# Netzteil_Darlington_v2.net
KiCad netlist of a schematic drawn in EAGLE
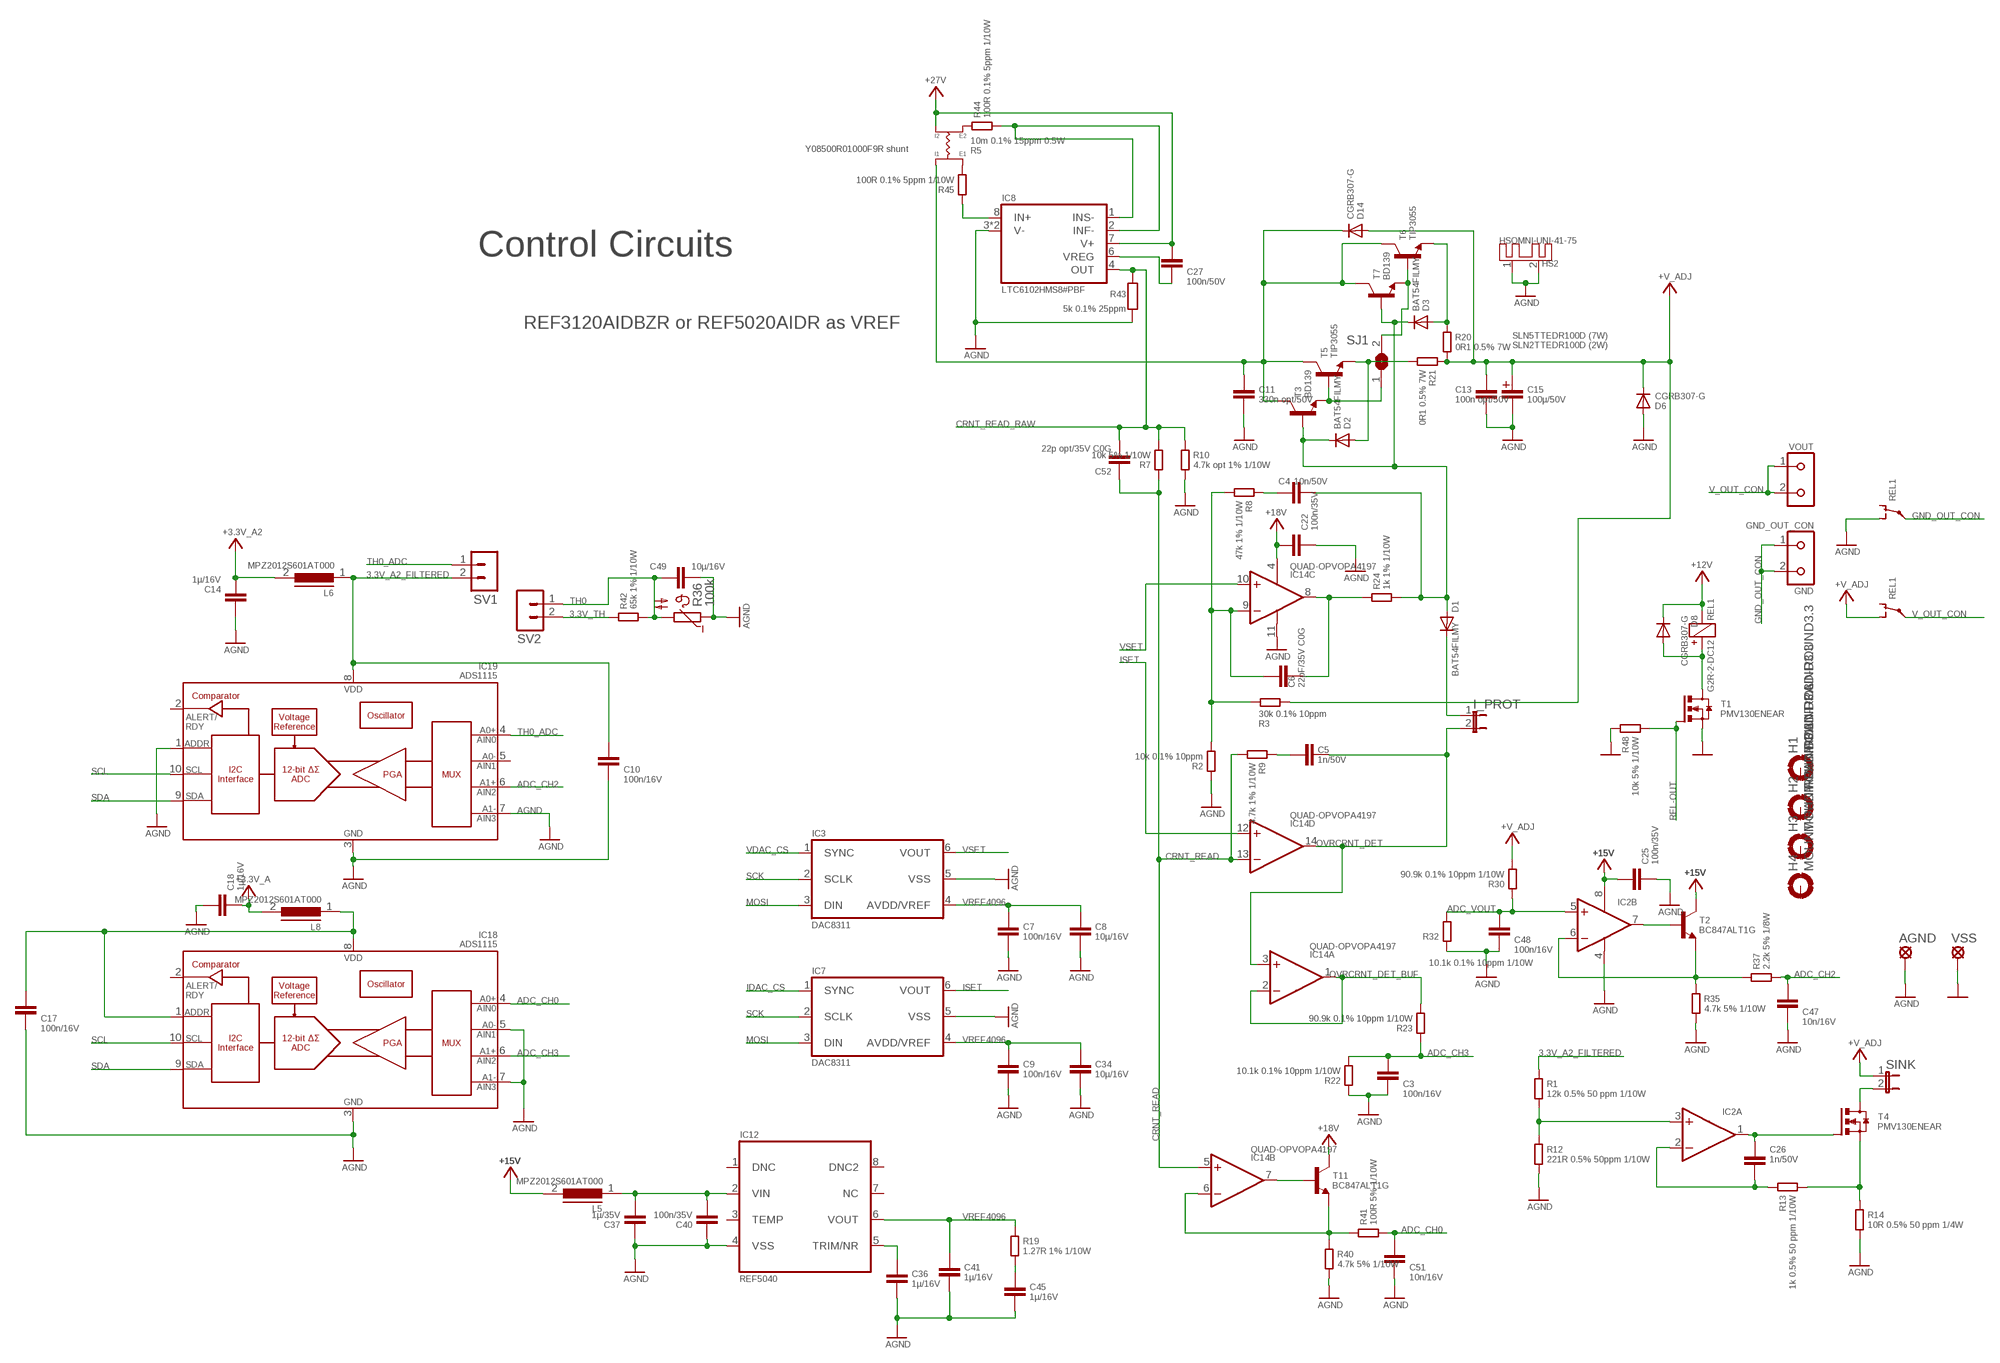
[diagram p0: schematic, sheet 1]
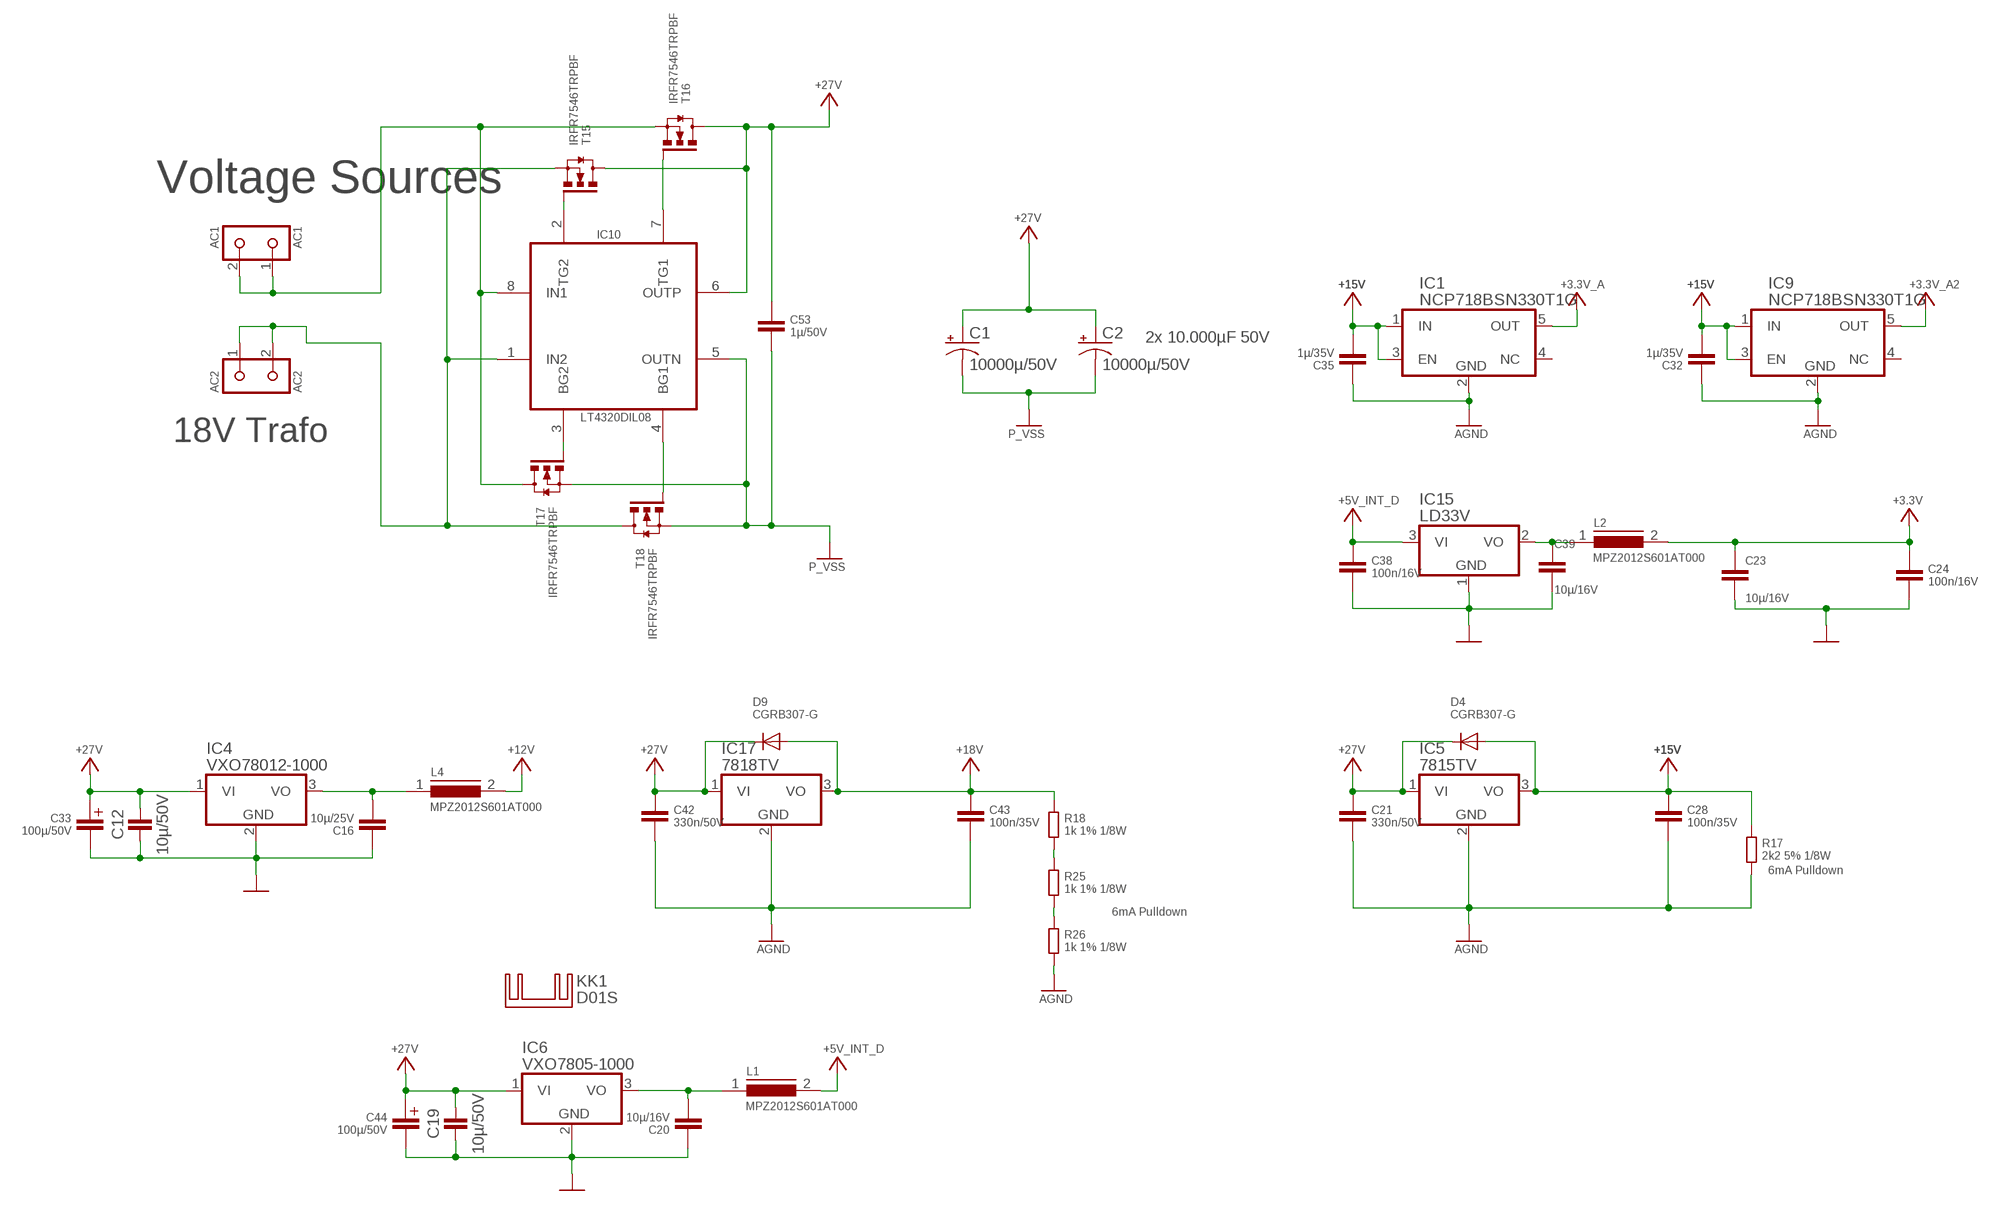
[diagram p1: schematic, sheet 2]
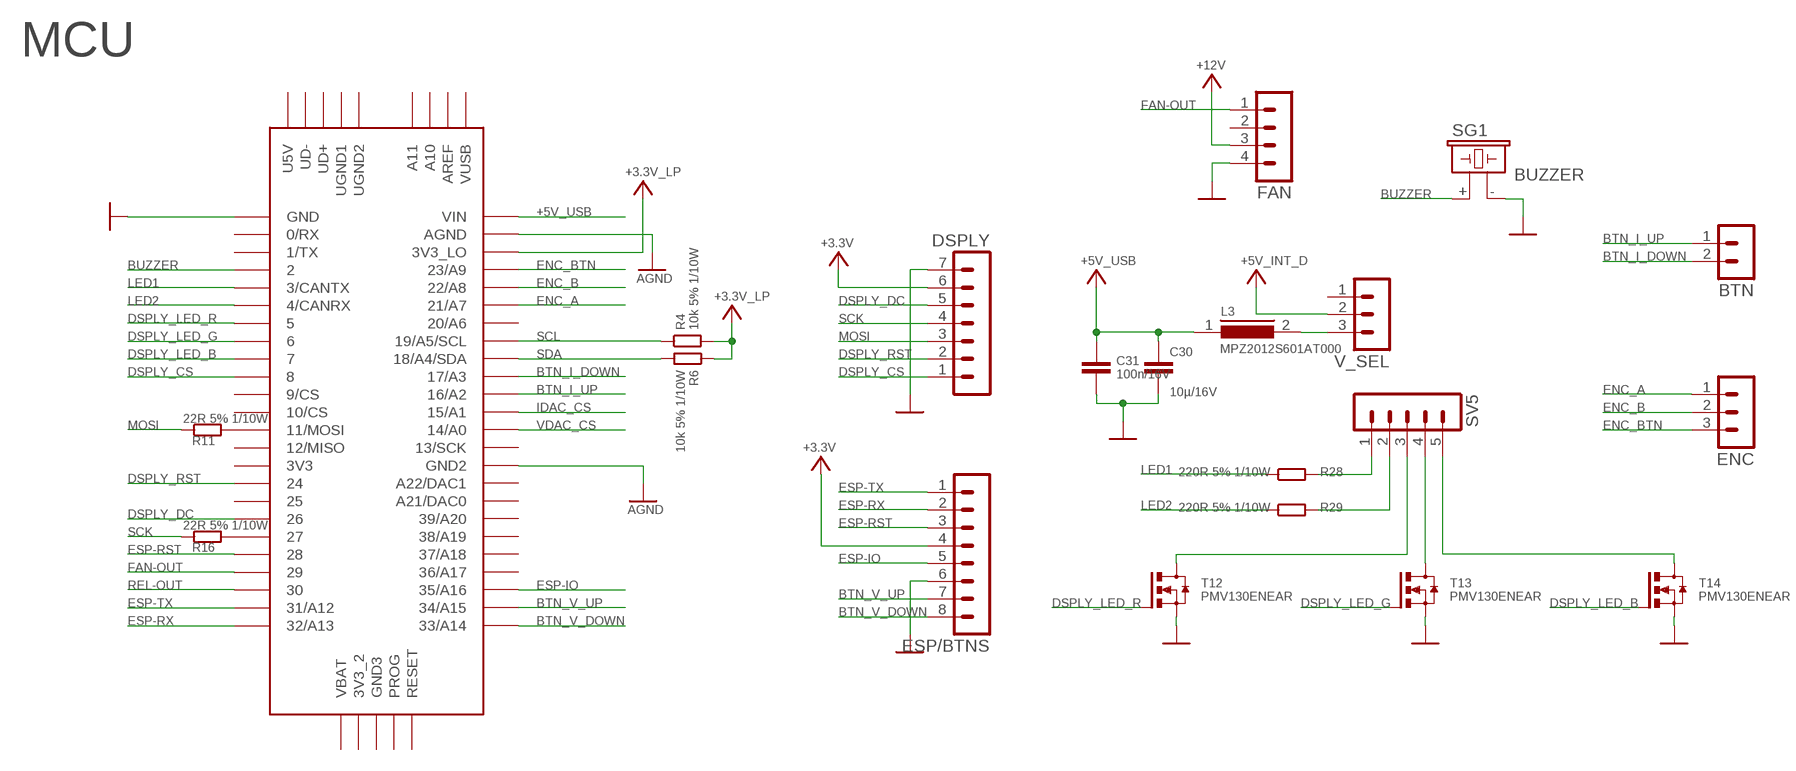
[diagram p2: schematic, sheet 3]

(export (version "E")
  (design (tool "Eeschema 10.0.6"))
  (components
    (comp (ref "AGND")
      (value "LSP13")
      (footprint "eagle-import:LSP13")
      (libsource (lib "eagle-import") (part "LSP13"))
    )
    (comp (ref "C3")
      (value "100n/16V")
      (footprint "eagle-import:0805")
      (libsource (lib "eagle-import") (part "CC/0805"))
    )
    (comp (ref "C4")
      (value "10n/50V")
      (footprint "eagle-import:0805")
      (libsource (lib "eagle-import") (part "CC/0805"))
    )
    (comp (ref "C5")
      (value "1n/50V")
      (footprint "eagle-import:0805")
      (libsource (lib "eagle-import") (part "CC/0805"))
    )
    (comp (ref "C6")
      (value "22pF/35V C0G")
      (footprint "eagle-import:0805")
      (libsource (lib "eagle-import") (part "CC/0805"))
    )
    (comp (ref "C7")
      (value "100n/16V")
      (footprint "eagle-import:0805")
      (libsource (lib "eagle-import") (part "CC/0805"))
    )
    (comp (ref "C8")
      (value "10µ/16V")
      (footprint "eagle-import:1206")
      (libsource (lib "eagle-import") (part "CC/1206"))
    )
    (comp (ref "C9")
      (value "100n/16V")
      (footprint "eagle-import:0805")
      (libsource (lib "eagle-import") (part "CC/0805"))
    )
    (comp (ref "C10")
      (value "100n/16V")
      (footprint "eagle-import:0805")
      (libsource (lib "eagle-import") (part "CC/0805"))
    )
    (comp (ref "C11")
      (value "330n opt/50V")
      (footprint "eagle-import:0805")
      (libsource (lib "eagle-import") (part "CC/0805"))
    )
    (comp (ref "C13")
      (value "100n opt/50V")
      (footprint "eagle-import:0805")
      (libsource (lib "eagle-import") (part "CC/0805"))
    )
    (comp (ref "C14")
      (value "1µ/16V")
      (footprint "eagle-import:0805")
      (libsource (lib "eagle-import") (part "CC/0805"))
    )
    (comp (ref "C15")
      (value "100µ/50V")
      (footprint "eagle-import:C+_3.5_8")
      (libsource (lib "eagle-import") (part "C+3.5/8"))
    )
    (comp (ref "C17")
      (value "100n/16V")
      (footprint "eagle-import:0805")
      (libsource (lib "eagle-import") (part "CC/0805"))
    )
    (comp (ref "C18")
      (value "1µ/16V")
      (footprint "eagle-import:0805")
      (libsource (lib "eagle-import") (part "CC/0805"))
    )
    (comp (ref "C22")
      (value "100n/35V")
      (footprint "eagle-import:0805")
      (libsource (lib "eagle-import") (part "CC/0805"))
    )
    (comp (ref "C25")
      (value "100n/35V")
      (footprint "eagle-import:0805")
      (libsource (lib "eagle-import") (part "CC/0805"))
    )
    (comp (ref "C26")
      (value "1n/50V")
      (footprint "eagle-import:0805")
      (libsource (lib "eagle-import") (part "CC/0805"))
    )
    (comp (ref "C27")
      (value "100n/50V")
      (footprint "eagle-import:0805")
      (libsource (lib "eagle-import") (part "CC/0805"))
    )
    (comp (ref "C34")
      (value "10µ/16V")
      (footprint "eagle-import:1206")
      (libsource (lib "eagle-import") (part "CC/1206"))
    )
    (comp (ref "C36")
      (value "1µ/16V")
      (footprint "eagle-import:0805")
      (libsource (lib "eagle-import") (part "CC/0805"))
    )
    (comp (ref "C37")
      (value "1µ/35V")
      (footprint "eagle-import:0805")
      (libsource (lib "eagle-import") (part "CC/0805"))
    )
    (comp (ref "C40")
      (value "100n/35V")
      (footprint "eagle-import:0805")
      (libsource (lib "eagle-import") (part "CC/0805"))
    )
    (comp (ref "C41")
      (value "1µ/16V")
      (footprint "eagle-import:0805")
      (libsource (lib "eagle-import") (part "CC/0805"))
    )
    (comp (ref "C45")
      (value "1µ/16V")
      (footprint "eagle-import:0805")
      (libsource (lib "eagle-import") (part "CC/0805"))
    )
    (comp (ref "C47")
      (value "10n/16V")
      (footprint "eagle-import:0805")
      (libsource (lib "eagle-import") (part "CC/0805"))
    )
    (comp (ref "C48")
      (value "100n/16V")
      (footprint "eagle-import:0805")
      (libsource (lib "eagle-import") (part "CC/0805"))
    )
    (comp (ref "C49")
      (value "10µ/16V")
      (footprint "eagle-import:1206")
      (libsource (lib "eagle-import") (part "CC/1206"))
    )
    (comp (ref "C51")
      (value "10n/16V")
      (footprint "eagle-import:0805")
      (libsource (lib "eagle-import") (part "CC/0805"))
    )
    (comp (ref "C52")
      (value "22p opt/35V C0G")
      (footprint "eagle-import:0805")
      (libsource (lib "eagle-import") (part "CC/0805"))
    )
    (comp (ref "D1")
      (value "BAT54FILMY")
      (footprint "eagle-import:SOT23")
      (libsource (lib "eagle-import") (part "DBAT54FILMY"))
    )
    (comp (ref "D2")
      (value "BAT54FILMY")
      (footprint "eagle-import:SOT23")
      (libsource (lib "eagle-import") (part "DBAT54FILMY"))
    )
    (comp (ref "D3")
      (value "BAT54FILMY")
      (footprint "eagle-import:SOT23")
      (libsource (lib "eagle-import") (part "DBAT54FILMY"))
    )
    (comp (ref "D6")
      (value "CGRB307-G")
      (footprint "eagle-import:DO214AA-CGRB307-G")
      (libsource (lib "eagle-import") (part "DWIDE"))
    )
    (comp (ref "D8")
      (value "CGRB307-G")
      (footprint "eagle-import:DO214AA-CGRB307-G")
      (libsource (lib "eagle-import") (part "DWIDE"))
    )
    (comp (ref "D14")
      (value "CGRB307-G")
      (footprint "eagle-import:DO214AA-CGRB307-G")
      (libsource (lib "eagle-import") (part "DWIDE"))
    )
    (comp (ref "GND_OUT_CON")
      (value "GND")
      (footprint "eagle-import:KL2-691311500002")
      (libsource (lib "eagle-import") (part "KL2691311500002"))
    )
    (comp (ref "H1")
      (value "MOUNT-PAD-ROUND3.3")
      (footprint "eagle-import:3,3-PAD")
      (libsource (lib "eagle-import") (part "MOUNT-PAD-ROUND3.3"))
    )
    (comp (ref "H2")
      (value "MOUNT-PAD-ROUND3.3")
      (footprint "eagle-import:3,3-PAD")
      (libsource (lib "eagle-import") (part "MOUNT-PAD-ROUND3.3"))
    )
    (comp (ref "H3")
      (value "MOUNT-PAD-ROUND3.3")
      (footprint "eagle-import:3,3-PAD")
      (libsource (lib "eagle-import") (part "MOUNT-PAD-ROUND3.3"))
    )
    (comp (ref "H4")
      (value "MOUNT-PAD-ROUND3.3")
      (footprint "eagle-import:3,3-PAD")
      (libsource (lib "eagle-import") (part "MOUNT-PAD-ROUND3.3"))
    )
    (comp (ref "HS2")
      (value "HSOMNI-UNI-41-75")
      (footprint "eagle-import:OMNI-UNI-41-75")
      (libsource (lib "eagle-import") (part "HSOMNI-UNI-41-75"))
    )
    (comp (ref "IC2")
      (value "DUAL-OPVSOP8")
      (footprint "eagle-import:SOP8")
      (libsource (lib "eagle-import") (part "DUAL-OPVSOP8"))
    )
    (comp (ref "IC3")
      (value "DAC8311")
      (footprint "eagle-import:SC-70-6")
      (libsource (lib "eagle-import") (part "DAC8X11"))
    )
    (comp (ref "IC7")
      (value "DAC8311")
      (footprint "eagle-import:SC-70-6")
      (libsource (lib "eagle-import") (part "DAC8X11"))
    )
    (comp (ref "IC8")
      (value "LTC6102HMS8#PBF")
      (footprint "eagle-import:MSOP8-0.65-3X3MM")
      (libsource (lib "eagle-import") (part "LTC6102"))
    )
    (comp (ref "IC12")
      (value "REF5040")
      (footprint "eagle-import:MSOP8-0.65-3X3MM")
      (libsource (lib "eagle-import") (part "REF50XXVSSOP8"))
    )
    (comp (ref "IC14")
      (value "QUAD-OPVOPA4197")
      (footprint "eagle-import:SO14")
      (libsource (lib "eagle-import") (part "QUAD-OPVOPA4197"))
    )
    (comp (ref "IC18")
      (value "ADS1115")
      (footprint "eagle-import:MSOP10")
      (libsource (lib "eagle-import") (part "ADS1015"))
    )
    (comp (ref "IC19")
      (value "ADS1115")
      (footprint "eagle-import:MSOP10")
      (libsource (lib "eagle-import") (part "ADS1015"))
    )
    (comp (ref "I_PROT")
      (value "JP1E")
      (footprint "eagle-import:JP1")
      (libsource (lib "eagle-import") (part "JP1E"))
    )
    (comp (ref "L5")
      (value "MPZ2012S601AT000")
      (footprint "eagle-import:C0805K")
      (libsource (lib "eagle-import") (part "L0805"))
    )
    (comp (ref "L6")
      (value "MPZ2012S601AT000")
      (footprint "eagle-import:C0805K")
      (libsource (lib "eagle-import") (part "L0805"))
    )
    (comp (ref "L8")
      (value "MPZ2012S601AT000")
      (footprint "eagle-import:C0805K")
      (libsource (lib "eagle-import") (part "L0805"))
    )
    (comp (ref "R1")
      (value "12k 0.5% 50 ppm 1/10W")
      (footprint "eagle-import:C0805K")
      (libsource (lib "eagle-import") (part "R-SMD0805"))
    )
    (comp (ref "R2")
      (value "10k 0.1% 10ppm")
      (footprint "eagle-import:C0805K")
      (libsource (lib "eagle-import") (part "R-SMD0805"))
    )
    (comp (ref "R3")
      (value "30k 0.1% 10ppm")
      (footprint "eagle-import:C0805K")
      (libsource (lib "eagle-import") (part "R-SMD0805"))
    )
    (comp (ref "R5")
      (value "10m 0.1% 15ppm 0.5W")
      (footprint "eagle-import:CSM2512")
      (libsource (lib "eagle-import") (part "R-CSM2512"))
    )
    (comp (ref "R7")
      (value "10k 5% 1/10W")
      (footprint "eagle-import:C0805K")
      (libsource (lib "eagle-import") (part "R-SMD0805"))
    )
    (comp (ref "R8")
      (value "47k 1% 1/10W")
      (footprint "eagle-import:C0805K")
      (libsource (lib "eagle-import") (part "R-SMD0805"))
    )
    (comp (ref "R9")
      (value "4.7k 1% 1/10W")
      (footprint "eagle-import:C0805K")
      (libsource (lib "eagle-import") (part "R-SMD0805"))
    )
    (comp (ref "R10")
      (value "4.7k opt 1% 1/10W")
      (footprint "eagle-import:C0805K")
      (libsource (lib "eagle-import") (part "R-SMD0805"))
    )
    (comp (ref "R12")
      (value "221R 0.5% 50ppm 1/10W")
      (footprint "eagle-import:C0805K")
      (libsource (lib "eagle-import") (part "R-SMD0805"))
    )
    (comp (ref "R13")
      (value "1k 0.5% 50 ppm 1/10W")
      (footprint "eagle-import:C0805K")
      (libsource (lib "eagle-import") (part "R-SMD0805"))
    )
    (comp (ref "R14")
      (value "10R 0.5% 50 ppm 1/4W")
      (footprint "eagle-import:C0805K")
      (libsource (lib "eagle-import") (part "R-SMD0805"))
    )
    (comp (ref "R19")
      (value "1.27R 1% 1/10W")
      (footprint "eagle-import:C0805K")
      (libsource (lib "eagle-import") (part "R-SMD0805"))
    )
    (comp (ref "R20")
      (value "0R1 0.5% 7W")
      (footprint "eagle-import:SLN2")
      (libsource (lib "eagle-import") (part "R-SMDSLN2"))
    )
    (comp (ref "R21")
      (value "0R1 0.5% 7W")
      (footprint "eagle-import:SLN2")
      (libsource (lib "eagle-import") (part "R-SMDSLN2"))
    )
    (comp (ref "R22")
      (value "10.1k 0.1% 10ppm 1/10W")
      (footprint "eagle-import:C0805K")
      (libsource (lib "eagle-import") (part "R-SMD0805"))
    )
    (comp (ref "R23")
      (value "90.9k 0.1% 10ppm 1/10W")
      (footprint "eagle-import:C0805K")
      (libsource (lib "eagle-import") (part "R-SMD0805"))
    )
    (comp (ref "R24")
      (value "1k 1% 1/10W")
      (footprint "eagle-import:C0805K")
      (libsource (lib "eagle-import") (part "R-SMD0805"))
    )
    (comp (ref "R30")
      (value "90.9k 0.1% 10ppm 1/10W")
      (footprint "eagle-import:C0805K")
      (libsource (lib "eagle-import") (part "R-SMD0805"))
    )
    (comp (ref "R32")
      (value "10.1k 0.1% 10ppm 1/10W")
      (footprint "eagle-import:C0805K")
      (libsource (lib "eagle-import") (part "R-SMD0805"))
    )
    (comp (ref "R35")
      (value "4.7k 5% 1/10W")
      (footprint "eagle-import:C0805K")
      (libsource (lib "eagle-import") (part "R-SMD0805"))
    )
    (comp (ref "R36")
      (value "100k")
      (footprint "eagle-import:P640")
      (libsource (lib "eagle-import") (part "NTC640"))
    )
    (comp (ref "R37")
      (value "2.2k 5% 1/8W")
      (footprint "eagle-import:C0805K")
      (libsource (lib "eagle-import") (part "R-SMD0805"))
    )
    (comp (ref "R40")
      (value "4.7k 5% 1/10W")
      (footprint "eagle-import:C0805K")
      (libsource (lib "eagle-import") (part "R-SMD0805"))
    )
    (comp (ref "R41")
      (value "100R 5% 1/10W")
      (footprint "eagle-import:C0805K")
      (libsource (lib "eagle-import") (part "R-SMD0805"))
    )
    (comp (ref "R42")
      (value "65k 1% 1/10W")
      (footprint "eagle-import:C0805K")
      (libsource (lib "eagle-import") (part "R-SMD0805"))
    )
    (comp (ref "R43")
      (value "5k 0.1% 25ppm")
      (footprint "eagle-import:R1206")
      (libsource (lib "eagle-import") (part "R-EU_R1206"))
    )
    (comp (ref "R44")
      (value "100R 0.1% 5ppm 1/10W")
      (footprint "eagle-import:C0805K")
      (libsource (lib "eagle-import") (part "R-SMD0805"))
    )
    (comp (ref "R45")
      (value "100R 0.1% 5ppm 1/10W")
      (footprint "eagle-import:C0805K")
      (libsource (lib "eagle-import") (part "R-SMD0805"))
    )
    (comp (ref "R48")
      (value "10k 5% 1/10W")
      (footprint "eagle-import:C0805K")
      (libsource (lib "eagle-import") (part "R-SMD0805"))
    )
    (comp (ref "REL1")
      (value "G2R-2-DC12")
      (footprint "eagle-import:REL-G2R2")
      (fields (field (name "OC_MOUSER") "653-G2R-2-DC12"))
      (libsource (lib "eagle-import") (part "REL-2UG2R2"))
    )
    (comp (ref "SINK")
      (value "JP1E")
      (footprint "eagle-import:JP1")
      (libsource (lib "eagle-import") (part "JP1E"))
    )
    (comp (ref "SJ1") (value "SJ") (footprint "eagle-import:SJ") (libsource (lib "eagle-import") (part "SJ")))
    (comp (ref "SV1")
      (value "JST-PH-2.0-2P")
      (footprint "eagle-import:JST-PH-2.0-2P")
      (libsource (lib "eagle-import") (part "JST-PH-2.0-2P"))
    )
    (comp (ref "SV2")
      (value "JST-PH-2.0-2P")
      (footprint "eagle-import:JST-PH-2.0-2P")
      (libsource (lib "eagle-import") (part "JST-PH-2.0-2P"))
    )
    (comp (ref "T1")
      (value "PMV130ENEAR")
      (footprint "eagle-import:SOT23")
      (libsource (lib "eagle-import") (part "neumluc_T-NMOSIRLML2502PBF"))
    )
    (comp (ref "T2")
      (value "BC847ALT1G")
      (footprint "eagle-import:SOT23-BEC")
      (libsource (lib "eagle-import") (part "T-NPNSOT23-BEC"))
    )
    (comp (ref "T3")
      (value "BD139")
      (footprint "eagle-import:TO126")
      (libsource (lib "eagle-import") (part "T-NPNTO126-ECB"))
    )
    (comp (ref "T4")
      (value "PMV130ENEAR")
      (footprint "eagle-import:SOT23")
      (libsource (lib "eagle-import") (part "neumluc_T-NMOSIRLML2502PBF"))
    )
    (comp (ref "T5")
      (value "TIP3055")
      (footprint "eagle-import:TOP3AV")
      (libsource (lib "eagle-import") (part "T-NPNTOP3AV-BCE"))
    )
    (comp (ref "T6")
      (value "TIP3055")
      (footprint "eagle-import:TOP3AV")
      (libsource (lib "eagle-import") (part "T-NPNTOP3AV-BCE"))
    )
    (comp (ref "T7")
      (value "BD139")
      (footprint "eagle-import:TO126")
      (libsource (lib "eagle-import") (part "T-NPNTO126-ECB"))
    )
    (comp (ref "T11")
      (value "BC847ALT1G")
      (footprint "eagle-import:SOT23-BEC")
      (libsource (lib "eagle-import") (part "T-NPNSOT23-BEC"))
    )
    (comp (ref "VOUT")
      (value "KL2691311500002")
      (footprint "eagle-import:KL2-691311500002")
      (libsource (lib "eagle-import") (part "KL2691311500002"))
    )
    (comp (ref "VSS")
      (value "LSP13")
      (footprint "eagle-import:LSP13")
      (libsource (lib "eagle-import") (part "LSP13"))
    )
    (comp (ref "BTN")
      (value "JST-PH-2.0-2P")
      (footprint "eagle-import:JST-PH-2.0-2P")
      (libsource (lib "eagle-import") (part "JST-PH-2.0-2P"))
    )
    (comp (ref "C30")
      (value "10µ/16V")
      (footprint "eagle-import:1206")
      (libsource (lib "eagle-import") (part "CC/1206"))
    )
    (comp (ref "C31")
      (value "100n/16V")
      (footprint "eagle-import:0805")
      (libsource (lib "eagle-import") (part "CC/0805"))
    )
    (comp (ref "DSPLY")
      (value "JST-PH-2.0-7P")
      (footprint "eagle-import:JST-PH-2.0-7P")
      (libsource (lib "eagle-import") (part "JST-PH-2.0-7P"))
    )
    (comp (ref "ENC")
      (value "JST-PH-2.0-3P")
      (footprint "eagle-import:JST-PH-2.0-3P")
      (libsource (lib "eagle-import") (part "JST-PH-2.0-3P"))
    )
    (comp (ref "ESP/BTNS")
      (value "JST-PH-2.0-8P")
      (footprint "eagle-import:JST-PH-2.0-8P")
      (libsource (lib "eagle-import") (part "JST-PH-2.0-8P"))
    )
    (comp (ref "FAN")
      (value "JST-PH-2.0-4P")
      (footprint "eagle-import:JST-PH-2.0-4P")
      (libsource (lib "eagle-import") (part "JST-PH-2.0-4P"))
    )
    (comp (ref "L3")
      (value "MPZ2012S601AT000")
      (footprint "eagle-import:C0805K")
      (libsource (lib "eagle-import") (part "L0805"))
    )
    (comp (ref "R4")
      (value "10k 5% 1/10W")
      (footprint "eagle-import:C0805K")
      (libsource (lib "eagle-import") (part "R-SMD0805"))
    )
    (comp (ref "R6")
      (value "10k 5% 1/10W")
      (footprint "eagle-import:C0805K")
      (libsource (lib "eagle-import") (part "R-SMD0805"))
    )
    (comp (ref "R11")
      (value "22R 5% 1/10W")
      (footprint "eagle-import:C0805K")
      (libsource (lib "eagle-import") (part "R-SMD0805"))
    )
    (comp (ref "R16")
      (value "22R 5% 1/10W")
      (footprint "eagle-import:C0805K")
      (libsource (lib "eagle-import") (part "R-SMD0805"))
    )
    (comp (ref "R28")
      (value "220R 5% 1/10W")
      (footprint "eagle-import:C0805K")
      (libsource (lib "eagle-import") (part "R-SMD0805"))
    )
    (comp (ref "R29")
      (value "220R 5% 1/10W")
      (footprint "eagle-import:C0805K")
      (libsource (lib "eagle-import") (part "R-SMD0805"))
    )
    (comp (ref "SG1")
      (value "BUZZER")
      (footprint "eagle-import:254-EMB73-RO")
      (libsource (lib "eagle-import") (part "BUZZER"))
    )
    (comp (ref "SV5")
      (value "JST-PH-2.0-5P")
      (footprint "eagle-import:JST-PH-2.0-5P")
      (libsource (lib "eagle-import") (part "JST-PH-2.0-5P"))
    )
    (comp (ref "T12")
      (value "PMV130ENEAR")
      (footprint "eagle-import:SOT23")
      (libsource (lib "eagle-import") (part "T-NMOSIRLML2502PBF"))
    )
    (comp (ref "T13")
      (value "PMV130ENEAR")
      (footprint "eagle-import:SOT23")
      (libsource (lib "eagle-import") (part "T-NMOSIRLML2502PBF"))
    )
    (comp (ref "T14")
      (value "PMV130ENEAR")
      (footprint "eagle-import:SOT23")
      (libsource (lib "eagle-import") (part "T-NMOSIRLML2502PBF"))
    )
    (comp (ref "U$33")
      (value "TEENSY_3.5/3.6")
      (footprint "eagle-import:TEENSY_3.5_3.6")
      (libsource (lib "eagle-import") (part "TEENSY_3.5/3.6"))
    )
    (comp (ref "V_SEL")
      (value "MA03-1")
      (footprint "eagle-import:MA03-1")
      (libsource (lib "eagle-import") (part "MA03-1"))
    )
    (comp (ref "AC1")
      (value "AC1")
      (footprint "eagle-import:KL2-691311500002")
      (libsource (lib "eagle-import") (part "KL2691311500002"))
    )
    (comp (ref "AC2")
      (value "AC2")
      (footprint "eagle-import:KL2-691311500002")
      (libsource (lib "eagle-import") (part "KL2691311500002"))
    )
    (comp (ref "C1")
      (value "10000µ/50V")
      (footprint "eagle-import:EB22,5D")
      (libsource (lib "eagle-import") (part "CPOL-USE10-22.5"))
    )
    (comp (ref "C2")
      (value "10000µ/50V")
      (footprint "eagle-import:EB22,5D")
      (libsource (lib "eagle-import") (part "CPOL-USE10-22.5"))
    )
    (comp (ref "C12")
      (value "10µ/50V")
      (footprint "eagle-import:C1210")
      (libsource (lib "eagle-import") (part "CAPACITOR-1210"))
    )
    (comp (ref "C16")
      (value "10µ/25V")
      (footprint "eagle-import:1206")
      (libsource (lib "eagle-import") (part "CC/1206"))
    )
    (comp (ref "C19")
      (value "10µ/50V")
      (footprint "eagle-import:C1210")
      (libsource (lib "eagle-import") (part "CAPACITOR-1210"))
    )
    (comp (ref "C20")
      (value "10µ/16V")
      (footprint "eagle-import:1206")
      (libsource (lib "eagle-import") (part "CC/1206"))
    )
    (comp (ref "C21")
      (value "330n/50V")
      (footprint "eagle-import:0805")
      (libsource (lib "eagle-import") (part "CC/0805"))
    )
    (comp (ref "C23")
      (value "10µ/16V")
      (footprint "eagle-import:1206")
      (libsource (lib "eagle-import") (part "CC/1206"))
    )
    (comp (ref "C24")
      (value "100n/16V")
      (footprint "eagle-import:0805")
      (libsource (lib "eagle-import") (part "CC/0805"))
    )
    (comp (ref "C28")
      (value "100n/35V")
      (footprint "eagle-import:0805")
      (libsource (lib "eagle-import") (part "CC/0805"))
    )
    (comp (ref "C32")
      (value "1µ/35V")
      (footprint "eagle-import:0805")
      (libsource (lib "eagle-import") (part "CC/0805"))
    )
    (comp (ref "C33")
      (value "100µ/50V")
      (footprint "eagle-import:C+_3.5_8")
      (libsource (lib "eagle-import") (part "C+3.5/8"))
    )
    (comp (ref "C35")
      (value "1µ/35V")
      (footprint "eagle-import:0805")
      (libsource (lib "eagle-import") (part "CC/0805"))
    )
    (comp (ref "C38")
      (value "100n/16V")
      (footprint "eagle-import:0805")
      (libsource (lib "eagle-import") (part "CC/0805"))
    )
    (comp (ref "C39")
      (value "10µ/16V")
      (footprint "eagle-import:1206")
      (libsource (lib "eagle-import") (part "CC/1206"))
    )
    (comp (ref "C42")
      (value "330n/50V")
      (footprint "eagle-import:0805")
      (libsource (lib "eagle-import") (part "CC/0805"))
    )
    (comp (ref "C43")
      (value "100n/35V")
      (footprint "eagle-import:0805")
      (libsource (lib "eagle-import") (part "CC/0805"))
    )
    (comp (ref "C44")
      (value "100µ/50V")
      (footprint "eagle-import:C+_3.5_8")
      (libsource (lib "eagle-import") (part "C+3.5/8"))
    )
    (comp (ref "C53")
      (value "1µ/50V")
      (footprint "eagle-import:1206")
      (libsource (lib "eagle-import") (part "CC/1206"))
    )
    (comp (ref "D4")
      (value "CGRB307-G")
      (footprint "eagle-import:DO214AA-CGRB307-G")
      (libsource (lib "eagle-import") (part "DWIDE"))
    )
    (comp (ref "D9")
      (value "CGRB307-G")
      (footprint "eagle-import:DO214AA-CGRB307-G")
      (libsource (lib "eagle-import") (part "DWIDE"))
    )
    (comp (ref "IC1")
      (value "NCP718BSN330T1G")
      (footprint "eagle-import:SOT23-5")
      (libsource (lib "eagle-import") (part "NCP718"))
    )
    (comp (ref "IC4")
      (value "VXO78012-1000")
      (footprint "eagle-import:78XX-DC-DC")
      (libsource (lib "eagle-import") (part "78XX-DC-DC-UNI-VXO-OKI"))
    )
    (comp (ref "IC5")
      (value "7815TV")
      (footprint "eagle-import:TO220V")
      (libsource (lib "eagle-import") (part "linear_262_78TV15"))
    )
    (comp (ref "IC6")
      (value "VXO7805-1000")
      (footprint "eagle-import:78XX-DC-DC")
      (libsource (lib "eagle-import") (part "78XX-DC-DC-UNI-VXO-OKI"))
    )
    (comp (ref "IC9")
      (value "NCP718BSN330T1G")
      (footprint "eagle-import:SOT23-5")
      (libsource (lib "eagle-import") (part "NCP718"))
    )
    (comp (ref "IC10")
      (value "LT4320DIL08")
      (footprint "eagle-import:DIL08")
      (libsource (lib "eagle-import") (part "LT4320DIL08"))
    )
    (comp (ref "IC15")
      (value "LD33V")
      (footprint "eagle-import:TO220V")
      (libsource (lib "eagle-import") (part "LD33V"))
    )
    (comp (ref "IC17")
      (value "7818TV")
      (footprint "eagle-import:TO220V")
      (libsource (lib "eagle-import") (part "78TV18"))
    )
    (comp (ref "KK1")
      (value "D01S")
      (footprint "eagle-import:D01S")
      (libsource (lib "eagle-import") (part "D01S"))
    )
    (comp (ref "L1")
      (value "MPZ2012S601AT000")
      (footprint "eagle-import:C0805K")
      (libsource (lib "eagle-import") (part "L0805"))
    )
    (comp (ref "L2")
      (value "MPZ2012S601AT000")
      (footprint "eagle-import:C0805K")
      (libsource (lib "eagle-import") (part "L0805"))
    )
    (comp (ref "L4")
      (value "MPZ2012S601AT000")
      (footprint "eagle-import:C0805K")
      (libsource (lib "eagle-import") (part "L0805"))
    )
    (comp (ref "R17")
      (value "2k2 5% 1/8W")
      (footprint "eagle-import:C0805K")
      (libsource (lib "eagle-import") (part "R-SMD0805"))
    )
    (comp (ref "R18")
      (value "1k 1% 1/8W")
      (footprint "eagle-import:C0805K")
      (libsource (lib "eagle-import") (part "R-SMD0805"))
    )
    (comp (ref "R25")
      (value "1k 1% 1/8W")
      (footprint "eagle-import:C0805K")
      (libsource (lib "eagle-import") (part "R-SMD0805"))
    )
    (comp (ref "R26")
      (value "1k 1% 1/8W")
      (footprint "eagle-import:C0805K")
      (libsource (lib "eagle-import") (part "R-SMD0805"))
    )
    (comp (ref "T15")
      (value "IRFR7546TRPBF")
      (footprint "eagle-import:DPACK")
      (libsource (lib "eagle-import") (part "neumluc_T-NMOSNTD4963N"))
    )
    (comp (ref "T16")
      (value "IRFR7546TRPBF")
      (footprint "eagle-import:DPACK")
      (libsource (lib "eagle-import") (part "neumluc_T-NMOSNTD4963N"))
    )
    (comp (ref "T17")
      (value "IRFR7546TRPBF")
      (footprint "eagle-import:DPACK")
      (libsource (lib "eagle-import") (part "neumluc_T-NMOSNTD4963N"))
    )
    (comp (ref "T18")
      (value "IRFR7546TRPBF")
      (footprint "eagle-import:DPACK")
      (libsource (lib "eagle-import") (part "neumluc_T-NMOSNTD4963N"))
    )
  )
  (nets
    (net (code "1") (name "+3.3V") (class "Default")
      (node (ref "C23") (pin "1") (pinfunction "1_1") (pintype "passive"))
      (node (ref "C24") (pin "1") (pinfunction "1_1") (pintype "passive"))
      (node (ref "DSPLY") (pin "6") (pinfunction "6_6") (pintype "passive"))
      (node (ref "ESP/BTNS") (pin "4") (pinfunction "4_4") (pintype "passive"))
      (node (ref "L2") (pin "2") (pinfunction "2_2") (pintype "passive"))
    )
    (net (code "2") (name "+3.3V_A") (class "Default")
      (node (ref "C18") (pin "2") (pinfunction "2_2") (pintype "passive"))
      (node (ref "IC1") (pin "5") (pinfunction "OUT_5") (pintype "passive"))
      (node (ref "L8") (pin "2") (pinfunction "2_2") (pintype "passive"))
    )
    (net (code "3") (name "+3.3V_A2") (class "Default")
      (node (ref "C14") (pin "2") (pinfunction "2_2") (pintype "passive"))
      (node (ref "IC9") (pin "5") (pinfunction "OUT_5") (pintype "passive"))
      (node (ref "L6") (pin "2") (pinfunction "2_2") (pintype "passive"))
    )
    (net (code "4") (name "+3.3V_LP") (class "Default")
      (node (ref "R4") (pin "2") (pinfunction "2_2") (pintype "passive"))
      (node (ref "R6") (pin "1") (pinfunction "1_1") (pintype "passive"))
      (node (ref "U$33") (pin "3V3_LO") (pinfunction "3V3_LO_3V3_LO") (pintype "bidirectional"))
    )
    (net (code "5") (name "+5V_INT_D") (class "Default")
      (node (ref "C38") (pin "1") (pinfunction "1_1") (pintype "passive"))
      (node (ref "IC15") (pin "3") (pinfunction "VI_3") (pintype "input"))
      (node (ref "L1") (pin "2") (pinfunction "2_2") (pintype "passive"))
      (node (ref "V_SEL") (pin "2") (pinfunction "2_2") (pintype "passive"))
    )
    (net (code "6") (name "+5V_USB") (class "Default")
      (node (ref "C30") (pin "1") (pinfunction "1_1") (pintype "passive"))
      (node (ref "C31") (pin "1") (pinfunction "1_1") (pintype "passive"))
      (node (ref "L3") (pin "1") (pinfunction "1_1") (pintype "passive"))
      (node (ref "U$33") (pin "VIN") (pinfunction "VIN_VIN") (pintype "bidirectional"))
    )
    (net (code "7") (name "+12V") (class "Default")
      (node (ref "D8") (pin "C") (pinfunction "C_C") (pintype "passive"))
      (node (ref "FAN") (pin "3") (pinfunction "3_3") (pintype "passive"))
      (node (ref "L4") (pin "2") (pinfunction "2_2") (pintype "passive"))
      (node (ref "REL1") (pin "-") (pinfunction "-_-") (pintype "passive"))
    )
    (net (code "8") (name "+15V") (class "Default")
      (node (ref "C25") (pin "1") (pinfunction "1_1") (pintype "passive"))
      (node (ref "C28") (pin "1") (pinfunction "1_1") (pintype "passive"))
      (node (ref "C32") (pin "2") (pinfunction "2_2") (pintype "passive"))
      (node (ref "C35") (pin "2") (pinfunction "2_2") (pintype "passive"))
      (node (ref "D4") (pin "A") (pinfunction "A_A") (pintype "passive"))
      (node (ref "IC1") (pin "1") (pinfunction "IN_1") (pintype "input"))
      (node (ref "IC1") (pin "3") (pinfunction "EN_3") (pintype "input"))
      (node (ref "IC2") (pin "8") (pinfunction "V+_8") (pintype "power_in"))
      (node (ref "IC5") (pin "3") (pinfunction "VO_3") (pintype "passive"))
      (node (ref "IC9") (pin "1") (pinfunction "IN_1") (pintype "input"))
      (node (ref "IC9") (pin "3") (pinfunction "EN_3") (pintype "input"))
      (node (ref "L5") (pin "2") (pinfunction "2_2") (pintype "passive"))
      (node (ref "R17") (pin "1") (pinfunction "1_1") (pintype "passive"))
      (node (ref "T2") (pin "C") (pinfunction "C_C") (pintype "passive"))
    )
    (net (code "9") (name "+18V") (class "Default")
      (node (ref "C22") (pin "1") (pinfunction "1_1") (pintype "passive"))
      (node (ref "C43") (pin "1") (pinfunction "1_1") (pintype "passive"))
      (node (ref "D9") (pin "A") (pinfunction "A_A") (pintype "passive"))
      (node (ref "IC14") (pin "4") (pinfunction "V+_4") (pintype "power_in"))
      (node (ref "IC17") (pin "3") (pinfunction "VO_3") (pintype "passive"))
      (node (ref "R18") (pin "1") (pinfunction "1_1") (pintype "passive"))
      (node (ref "T11") (pin "C") (pinfunction "C_C") (pintype "passive"))
    )
    (net (code "10") (name "+27V") (class "Default")
      (node (ref "C1") (pin "+") (pinfunction "+_+") (pintype "passive"))
      (node (ref "C12") (pin "2") (pinfunction "2_2") (pintype "passive"))
      (node (ref "C19") (pin "2") (pinfunction "2_2") (pintype "passive"))
      (node (ref "C2") (pin "+") (pinfunction "+_+") (pintype "passive"))
      (node (ref "C21") (pin "1") (pinfunction "1_1") (pintype "passive"))
      (node (ref "C27") (pin "1") (pinfunction "1_1") (pintype "passive"))
      (node (ref "C33") (pin "+") (pinfunction "+_+") (pintype "passive"))
      (node (ref "C42") (pin "1") (pinfunction "1_1") (pintype "passive"))
      (node (ref "C44") (pin "+") (pinfunction "+_+") (pintype "passive"))
      (node (ref "C53") (pin "1") (pinfunction "1_1") (pintype "passive"))
      (node (ref "D4") (pin "C") (pinfunction "C_C") (pintype "passive"))
      (node (ref "D9") (pin "C") (pinfunction "C_C") (pintype "passive"))
      (node (ref "IC10") (pin "6") (pinfunction "OUTP_6") (pintype "bidirectional"))
      (node (ref "IC17") (pin "1") (pinfunction "VI_1") (pintype "input"))
      (node (ref "IC4") (pin "1") (pinfunction "VI_1") (pintype "input"))
      (node (ref "IC5") (pin "1") (pinfunction "VI_1") (pintype "input"))
      (node (ref "IC6") (pin "1") (pinfunction "VI_1") (pintype "input"))
      (node (ref "IC8") (pin "7") (pinfunction "V+_7") (pintype "power_in"))
      (node (ref "R5") (pin "I2") (pinfunction "I2_I2") (pintype "passive"))
      (node (ref "T15") (pin "3") (pinfunction "D_3") (pintype "passive"))
      (node (ref "T16") (pin "3") (pinfunction "D_3") (pintype "passive"))
    )
    (net (code "11") (name "+V_ADJ") (class "Default")
      (node (ref "C13") (pin "1") (pinfunction "1_1") (pintype "passive"))
      (node (ref "C15") (pin "+") (pinfunction "+_+") (pintype "passive"))
      (node (ref "D14") (pin "A") (pinfunction "A_A") (pintype "passive"))
      (node (ref "D6") (pin "C") (pinfunction "C_C") (pintype "passive"))
      (node (ref "R20") (pin "2") (pinfunction "2_2") (pintype "passive"))
      (node (ref "R21") (pin "1") (pinfunction "1_1") (pintype "passive"))
      (node (ref "R3") (pin "1") (pinfunction "1_1") (pintype "passive"))
      (node (ref "R30") (pin "2") (pinfunction "2_2") (pintype "passive"))
      (node (ref "REL1") (pin "S1") (pinfunction "S_S1") (pintype "passive"))
      (node (ref "SINK") (pin "1") (pinfunction "1_1") (pintype "passive"))
    )
    (net (code "12") (name "3.3V_A2_FILTERED") (class "Default")
      (node (ref "C10") (pin "1") (pinfunction "1_1") (pintype "passive"))
      (node (ref "IC19") (pin "8") (pinfunction "VDD_8") (pintype "bidirectional"))
      (node (ref "L6") (pin "1") (pinfunction "1_1") (pintype "passive"))
      (node (ref "R1") (pin "1") (pinfunction "1_1") (pintype "passive"))
      (node (ref "SV1") (pin "2") (pinfunction "2_2") (pintype "passive"))
    )
    (net (code "13") (name "3.3V_TH") (class "Default")
      (node (ref "R42") (pin "1") (pinfunction "1_1") (pintype "passive"))
      (node (ref "SV2") (pin "2") (pinfunction "2_2") (pintype "passive"))
    )
    (net (code "14") (name "ADC_CH0") (class "Default")
      (node (ref "C51") (pin "1") (pinfunction "1_1") (pintype "passive"))
      (node (ref "IC18") (pin "4") (pinfunction "AIN0_4") (pintype "bidirectional"))
      (node (ref "R41") (pin "2") (pinfunction "2_2") (pintype "passive"))
    )
    (net (code "15") (name "ADC_CH2") (class "Default")
      (node (ref "C47") (pin "1") (pinfunction "1_1") (pintype "passive"))
      (node (ref "IC19") (pin "6") (pinfunction "AIN2_6") (pintype "bidirectional"))
      (node (ref "R37") (pin "2") (pinfunction "2_2") (pintype "passive"))
    )
    (net (code "16") (name "ADC_CH3") (class "Default")
      (node (ref "C3") (pin "1") (pinfunction "1_1") (pintype "passive"))
      (node (ref "IC18") (pin "6") (pinfunction "AIN2_6") (pintype "bidirectional"))
      (node (ref "R22") (pin "2") (pinfunction "2_2") (pintype "passive"))
      (node (ref "R23") (pin "1") (pinfunction "1_1") (pintype "passive"))
    )
    (net (code "17") (name "ADC_VOUT") (class "Default")
      (node (ref "C48") (pin "1") (pinfunction "1_1") (pintype "passive"))
      (node (ref "IC2") (pin "5") (pinfunction "+IN_5") (pintype "input"))
      (node (ref "R30") (pin "1") (pinfunction "1_1") (pintype "passive"))
      (node (ref "R32") (pin "2") (pinfunction "2_2") (pintype "passive"))
    )
    (net (code "18") (name "AGND") (class "Default")
      (node (ref "AGND") (pin "MP") (pinfunction "MP_MP") (pintype "passive"))
      (node (ref "C10") (pin "2") (pinfunction "2_2") (pintype "passive"))
      (node (ref "C11") (pin "2") (pinfunction "2_2") (pintype "passive"))
      (node (ref "C13") (pin "2") (pinfunction "2_2") (pintype "passive"))
      (node (ref "C14") (pin "1") (pinfunction "1_1") (pintype "passive"))
      (node (ref "C15") (pin "-") (pinfunction "-_-") (pintype "passive"))
      (node (ref "C17") (pin "2") (pinfunction "2_2") (pintype "passive"))
      (node (ref "C18") (pin "1") (pinfunction "1_1") (pintype "passive"))
      (node (ref "C21") (pin "2") (pinfunction "2_2") (pintype "passive"))
      (node (ref "C22") (pin "2") (pinfunction "2_2") (pintype "passive"))
      (node (ref "C25") (pin "2") (pinfunction "2_2") (pintype "passive"))
      (node (ref "C28") (pin "2") (pinfunction "2_2") (pintype "passive"))
      (node (ref "C3") (pin "2") (pinfunction "2_2") (pintype "passive"))
      (node (ref "C32") (pin "1") (pinfunction "1_1") (pintype "passive"))
      (node (ref "C34") (pin "2") (pinfunction "2_2") (pintype "passive"))
      (node (ref "C35") (pin "1") (pinfunction "1_1") (pintype "passive"))
      (node (ref "C36") (pin "2") (pinfunction "2_2") (pintype "passive"))
      (node (ref "C37") (pin "1") (pinfunction "1_1") (pintype "passive"))
      (node (ref "C40") (pin "1") (pinfunction "1_1") (pintype "passive"))
      (node (ref "C41") (pin "2") (pinfunction "2_2") (pintype "passive"))
      (node (ref "C42") (pin "2") (pinfunction "2_2") (pintype "passive"))
      (node (ref "C43") (pin "2") (pinfunction "2_2") (pintype "passive"))
      (node (ref "C45") (pin "2") (pinfunction "2_2") (pintype "passive"))
      (node (ref "C47") (pin "2") (pinfunction "2_2") (pintype "passive"))
      (node (ref "C48") (pin "2") (pinfunction "2_2") (pintype "passive"))
      (node (ref "C49") (pin "1") (pinfunction "1_1") (pintype "passive"))
      (node (ref "C51") (pin "2") (pinfunction "2_2") (pintype "passive"))
      (node (ref "C7") (pin "2") (pinfunction "2_2") (pintype "passive"))
      (node (ref "C8") (pin "2") (pinfunction "2_2") (pintype "passive"))
      (node (ref "C9") (pin "2") (pinfunction "2_2") (pintype "passive"))
      (node (ref "D6") (pin "A") (pinfunction "A_A") (pintype "passive"))
      (node (ref "HS2") (pin "1") (pinfunction "1_1") (pintype "passive"))
      (node (ref "HS2") (pin "2") (pinfunction "2_2") (pintype "passive"))
      (node (ref "IC1") (pin "2") (pinfunction "GND_2") (pintype "passive"))
      (node (ref "IC12") (pin "4") (pinfunction "VSS_4") (pintype "power_in"))
      (node (ref "IC14") (pin "11") (pinfunction "V-_11") (pintype "power_in"))
      (node (ref "IC17") (pin "2") (pinfunction "GND_2") (pintype "passive"))
      (node (ref "IC18") (pin "3") (pinfunction "VSS_3") (pintype "bidirectional"))
      (node (ref "IC18") (pin "5") (pinfunction "AIN1_5") (pintype "bidirectional"))
      (node (ref "IC18") (pin "7") (pinfunction "AIN3_7") (pintype "bidirectional"))
      (node (ref "IC19") (pin "1") (pinfunction "ADDR_1") (pintype "bidirectional"))
      (node (ref "IC19") (pin "3") (pinfunction "VSS_3") (pintype "bidirectional"))
      (node (ref "IC19") (pin "7") (pinfunction "AIN3_7") (pintype "bidirectional"))
      (node (ref "IC2") (pin "4") (pinfunction "V-_4") (pintype "power_in"))
      (node (ref "IC3") (pin "5") (pinfunction "VSS_5") (pintype "power_in"))
      (node (ref "IC5") (pin "2") (pinfunction "GND_2") (pintype "passive"))
      (node (ref "IC7") (pin "5") (pinfunction "VSS_5") (pintype "power_in"))
      (node (ref "IC8") (pin "3") (pinfunction "V-_3") (pintype "power_in"))
      (node (ref "IC8") (pin "5") (pinfunction "V-_5") (pintype "power_in"))
      (node (ref "IC9") (pin "2") (pinfunction "GND_2") (pintype "passive"))
      (node (ref "R10") (pin "2") (pinfunction "2_2") (pintype "passive"))
      (node (ref "R12") (pin "2") (pinfunction "2_2") (pintype "passive"))
      (node (ref "R14") (pin "2") (pinfunction "2_2") (pintype "passive"))
      (node (ref "R17") (pin "2") (pinfunction "2_2") (pintype "passive"))
      (node (ref "R2") (pin "1") (pinfunction "1_1") (pintype "passive"))
      (node (ref "R22") (pin "1") (pinfunction "1_1") (pintype "passive"))
      (node (ref "R26") (pin "2") (pinfunction "2_2") (pintype "passive"))
      (node (ref "R32") (pin "1") (pinfunction "1_1") (pintype "passive"))
      (node (ref "R35") (pin "2") (pinfunction "2_2") (pintype "passive"))
      (node (ref "R36") (pin "1") (pinfunction "1_1") (pintype "passive"))
      (node (ref "R40") (pin "2") (pinfunction "2_2") (pintype "passive"))
      (node (ref "R43") (pin "1") (pinfunction "1_1") (pintype "passive"))
      (node (ref "REL1") (pin "S2") (pinfunction "S_S2") (pintype "passive"))
      (node (ref "U$33") (pin "AGND") (pinfunction "AGND_AGND") (pintype "bidirectional"))
      (node (ref "U$33") (pin "GND2") (pinfunction "GND2_GND2") (pintype "bidirectional"))
    )
    (net (code "19") (name "BTN_I_DOWN") (class "Default")
      (node (ref "BTN") (pin "2") (pinfunction "2_2") (pintype "passive"))
      (node (ref "U$33") (pin "17/A3") (pinfunction "17/A3_17/A3") (pintype "bidirectional"))
    )
    (net (code "20") (name "BTN_I_UP") (class "Default")
      (node (ref "BTN") (pin "1") (pinfunction "1_1") (pintype "passive"))
      (node (ref "U$33") (pin "16/A2") (pinfunction "16/A2_16/A2") (pintype "bidirectional"))
    )
    (net (code "21") (name "BTN_V_DOWN") (class "Default")
      (node (ref "ESP/BTNS") (pin "8") (pinfunction "8_8") (pintype "passive"))
      (node (ref "U$33") (pin "33/A14") (pinfunction "33/A14_33/A14") (pintype "bidirectional"))
    )
    (net (code "22") (name "BTN_V_UP") (class "Default")
      (node (ref "ESP/BTNS") (pin "7") (pinfunction "7_7") (pintype "passive"))
      (node (ref "U$33") (pin "34/A15") (pinfunction "34/A15_34/A15") (pintype "bidirectional"))
    )
    (net (code "23") (name "BUZZER") (class "Default")
      (node (ref "SG1") (pin "+") (pinfunction "1_+") (pintype "passive"))
      (node (ref "U$33") (pin "2") (pinfunction "2_2") (pintype "bidirectional"))
    )
    (net (code "24") (name "CRNT_READ") (class "Default")
      (node (ref "C52") (pin "1") (pinfunction "1_1") (pintype "passive"))
      (node (ref "IC14") (pin "13") (pinfunction "-IN_13") (pintype "input"))
      (node (ref "IC14") (pin "5") (pinfunction "+IN_5") (pintype "input"))
      (node (ref "R7") (pin "1") (pinfunction "1_1") (pintype "passive"))
      (node (ref "R9") (pin "2") (pinfunction "2_2") (pintype "passive"))
    )
    (net (code "25") (name "CRNT_READ_RAW") (class "Default")
      (node (ref "C52") (pin "2") (pinfunction "2_2") (pintype "passive"))
      (node (ref "IC8") (pin "4") (pinfunction "OUT_4") (pintype "bidirectional"))
      (node (ref "R10") (pin "1") (pinfunction "1_1") (pintype "passive"))
      (node (ref "R43") (pin "2") (pinfunction "2_2") (pintype "passive"))
      (node (ref "R7") (pin "2") (pinfunction "2_2") (pintype "passive"))
    )
    (net (code "26") (name "DSPLY_CS") (class "Default")
      (node (ref "DSPLY") (pin "1") (pinfunction "1_1") (pintype "passive"))
      (node (ref "U$33") (pin "8") (pinfunction "8_8") (pintype "bidirectional"))
    )
    (net (code "27") (name "DSPLY_DC") (class "Default")
      (node (ref "DSPLY") (pin "5") (pinfunction "5_5") (pintype "passive"))
      (node (ref "U$33") (pin "26") (pinfunction "26_26") (pintype "bidirectional"))
    )
    (net (code "28") (name "DSPLY_LED_B") (class "Default")
      (node (ref "T14") (pin "1") (pinfunction "G_1") (pintype "passive"))
      (node (ref "U$33") (pin "7") (pinfunction "7_7") (pintype "bidirectional"))
    )
    (net (code "29") (name "DSPLY_LED_G") (class "Default")
      (node (ref "T13") (pin "1") (pinfunction "G_1") (pintype "passive"))
      (node (ref "U$33") (pin "6") (pinfunction "6_6") (pintype "bidirectional"))
    )
    (net (code "30") (name "DSPLY_LED_R") (class "Default")
      (node (ref "T12") (pin "1") (pinfunction "G_1") (pintype "passive"))
      (node (ref "U$33") (pin "5") (pinfunction "5_5") (pintype "bidirectional"))
    )
    (net (code "31") (name "DSPLY_RST") (class "Default")
      (node (ref "DSPLY") (pin "2") (pinfunction "2_2") (pintype "passive"))
      (node (ref "U$33") (pin "24") (pinfunction "24_24") (pintype "bidirectional"))
    )
    (net (code "32") (name "ENC_A") (class "Default")
      (node (ref "ENC") (pin "1") (pinfunction "1_1") (pintype "passive"))
      (node (ref "U$33") (pin "21/A7") (pinfunction "21/A7_21/A7") (pintype "bidirectional"))
    )
    (net (code "33") (name "ENC_B") (class "Default")
      (node (ref "ENC") (pin "2") (pinfunction "2_2") (pintype "passive"))
      (node (ref "U$33") (pin "22/A8") (pinfunction "22/A8_22/A8") (pintype "bidirectional"))
    )
    (net (code "34") (name "ENC_BTN") (class "Default")
      (node (ref "ENC") (pin "3") (pinfunction "3_3") (pintype "passive"))
      (node (ref "U$33") (pin "23/A9") (pinfunction "23/A9_23/A9") (pintype "bidirectional"))
    )
    (net (code "35") (name "ESP-IO") (class "Default")
      (node (ref "ESP/BTNS") (pin "5") (pinfunction "5_5") (pintype "passive"))
      (node (ref "U$33") (pin "35/A16") (pinfunction "35/A16_35/A16") (pintype "bidirectional"))
    )
    (net (code "36") (name "ESP-RST") (class "Default")
      (node (ref "ESP/BTNS") (pin "3") (pinfunction "3_3") (pintype "passive"))
      (node (ref "U$33") (pin "28") (pinfunction "28_28") (pintype "bidirectional"))
    )
    (net (code "37") (name "ESP-RX") (class "Default")
      (node (ref "ESP/BTNS") (pin "2") (pinfunction "2_2") (pintype "passive"))
      (node (ref "U$33") (pin "32/A13") (pinfunction "32/A13_32/A13") (pintype "bidirectional"))
    )
    (net (code "38") (name "ESP-TX") (class "Default")
      (node (ref "ESP/BTNS") (pin "1") (pinfunction "1_1") (pintype "passive"))
      (node (ref "U$33") (pin "31/A12") (pinfunction "31/A12_31/A12") (pintype "bidirectional"))
    )
    (net (code "39") (name "FAN-OUT") (class "Default")
      (node (ref "FAN") (pin "1") (pinfunction "1_1") (pintype "passive"))
      (node (ref "U$33") (pin "29") (pinfunction "29_29") (pintype "bidirectional"))
    )
    (net (code "40") (name "GND_OUT_CON") (class "Default")
      (node (ref "GND_OUT_CON") (pin "1") (pinfunction "1_1") (pintype "passive"))
      (node (ref "GND_OUT_CON") (pin "2") (pinfunction "2_2") (pintype "passive"))
      (node (ref "REL1") (pin "P2") (pinfunction "P_P2") (pintype "passive"))
    )
    (net (code "41") (name "IDAC_CS") (class "Default")
      (node (ref "IC7") (pin "1") (pinfunction "SYNC_1") (pintype "input"))
      (node (ref "U$33") (pin "15/A1") (pinfunction "15/A1_15/A1") (pintype "bidirectional"))
    )
    (net (code "42") (name "ISET") (class "Default")
      (node (ref "IC14") (pin "12") (pinfunction "+IN_12") (pintype "input"))
      (node (ref "IC7") (pin "6") (pinfunction "VOUT_6") (pintype "output"))
    )
    (net (code "43") (name "LED1") (class "Default")
      (node (ref "R28") (pin "1") (pinfunction "1_1") (pintype "passive"))
      (node (ref "U$33") (pin "3/CANTX") (pinfunction "3/CANTX_3/CANTX") (pintype "bidirectional"))
    )
    (net (code "44") (name "LED2") (class "Default")
      (node (ref "R29") (pin "1") (pinfunction "1_1") (pintype "passive"))
      (node (ref "U$33") (pin "4/CANRX") (pinfunction "4/CANRX_4/CANRX") (pintype "bidirectional"))
    )
    (net (code "45") (name "MOSI") (class "Default")
      (node (ref "DSPLY") (pin "3") (pinfunction "3_3") (pintype "passive"))
      (node (ref "IC3") (pin "3") (pinfunction "DIN_3") (pintype "bidirectional"))
      (node (ref "IC7") (pin "3") (pinfunction "DIN_3") (pintype "bidirectional"))
      (node (ref "R11") (pin "1") (pinfunction "1_1") (pintype "passive"))
    )
    (net (code "46") (name "Net-(C4-Pad1)") (class "Default")
      (node (ref "C4") (pin "1") (pinfunction "1_1") (pintype "passive"))
      (node (ref "R8") (pin "1") (pinfunction "1_1") (pintype "passive"))
    )
    (net (code "47") (name "Net-(C5-Pad1)") (class "Default")
      (node (ref "C5") (pin "1") (pinfunction "1_1") (pintype "passive"))
      (node (ref "R9") (pin "1") (pinfunction "1_1") (pintype "passive"))
    )
    (net (code "48") (name "Net-(C45-Pad1)") (class "Default")
      (node (ref "C45") (pin "1") (pinfunction "1_1") (pintype "passive"))
      (node (ref "R19") (pin "2") (pinfunction "2_2") (pintype "passive"))
    )
    (net (code "49") (name "Net-(D1-A)") (class "Default")
      (node (ref "C4") (pin "2") (pinfunction "2_2") (pintype "passive"))
      (node (ref "D1") (pin "1") (pinfunction "A_1") (pintype "passive"))
      (node (ref "D2") (pin "3") (pinfunction "C_3") (pintype "passive"))
      (node (ref "D3") (pin "3") (pinfunction "C_3") (pintype "passive"))
      (node (ref "R24") (pin "2") (pinfunction "2_2") (pintype "passive"))
      (node (ref "T3") (pin "3") (pinfunction "B_3") (pintype "passive"))
      (node (ref "T7") (pin "3") (pinfunction "B_3") (pintype "passive"))
    )
    (net (code "50") (name "Net-(D1-C)") (class "Default")
      (node (ref "D1") (pin "3") (pinfunction "C_3") (pintype "passive"))
      (node (ref "I_PROT") (pin "1") (pinfunction "1_1") (pintype "passive"))
    )
    (net (code "51") (name "Net-(D2-A)") (class "Default")
      (node (ref "D2") (pin "1") (pinfunction "A_1") (pintype "passive"))
      (node (ref "R21") (pin "2") (pinfunction "2_2") (pintype "passive"))
      (node (ref "T5") (pin "E") (pinfunction "E_E") (pintype "passive"))
    )
    (net (code "52") (name "Net-(D3-A)") (class "Default")
      (node (ref "D3") (pin "1") (pinfunction "A_1") (pintype "passive"))
      (node (ref "R20") (pin "1") (pinfunction "1_1") (pintype "passive"))
      (node (ref "T6") (pin "E") (pinfunction "E_E") (pintype "passive"))
    )
    (net (code "53") (name "Net-(IC2A-+IN)") (class "Default")
      (node (ref "IC2") (pin "3") (pinfunction "+IN_3") (pintype "input"))
      (node (ref "R1") (pin "2") (pinfunction "2_2") (pintype "passive"))
      (node (ref "R12") (pin "1") (pinfunction "1_1") (pintype "passive"))
    )
    (net (code "54") (name "Net-(IC2A--IN)") (class "Default")
      (node (ref "C26") (pin "2") (pinfunction "2_2") (pintype "passive"))
      (node (ref "IC2") (pin "2") (pinfunction "-IN_2") (pintype "input"))
      (node (ref "R13") (pin "1") (pinfunction "1_1") (pintype "passive"))
    )
    (net (code "55") (name "Net-(IC2A-OUT)") (class "Default")
      (node (ref "C26") (pin "1") (pinfunction "1_1") (pintype "passive"))
      (node (ref "IC2") (pin "1") (pinfunction "OUT_1") (pintype "output"))
      (node (ref "T4") (pin "1") (pinfunction "G_1") (pintype "passive"))
    )
    (net (code "56") (name "Net-(IC2B--IN)") (class "Default")
      (node (ref "IC2") (pin "6") (pinfunction "-IN_6") (pintype "input"))
      (node (ref "R35") (pin "1") (pinfunction "1_1") (pintype "passive"))
      (node (ref "R37") (pin "1") (pinfunction "1_1") (pintype "passive"))
      (node (ref "T2") (pin "E") (pinfunction "E_E") (pintype "passive"))
    )
    (net (code "57") (name "Net-(IC2B-OUT)") (class "Default")
      (node (ref "IC2") (pin "7") (pinfunction "OUT_7") (pintype "output"))
      (node (ref "T2") (pin "B") (pinfunction "B_B") (pintype "passive"))
    )
    (net (code "58") (name "Net-(IC4-VO)") (class "Default")
      (node (ref "C16") (pin "2") (pinfunction "2_2") (pintype "passive"))
      (node (ref "IC4") (pin "3") (pinfunction "VO_3") (pintype "passive"))
      (node (ref "L4") (pin "1") (pinfunction "1_1") (pintype "passive"))
    )
    (net (code "59") (name "Net-(IC6-VO)") (class "Default")
      (node (ref "C20") (pin "2") (pinfunction "2_2") (pintype "passive"))
      (node (ref "IC6") (pin "3") (pinfunction "VO_3") (pintype "passive"))
      (node (ref "L1") (pin "1") (pinfunction "1_1") (pintype "passive"))
    )
    (net (code "60") (name "Net-(IC8-IN+)") (class "Default")
      (node (ref "IC8") (pin "8") (pinfunction "IN+_8") (pintype "input"))
      (node (ref "R45") (pin "1") (pinfunction "1_1") (pintype "passive"))
    )
    (net (code "61") (name "Net-(IC8-INF-)") (class "Default")
      (node (ref "IC8") (pin "1") (pinfunction "INS-_1") (pintype "input"))
      (node (ref "IC8") (pin "2") (pinfunction "INF-_2") (pintype "bidirectional"))
      (node (ref "R44") (pin "2") (pinfunction "2_2") (pintype "passive"))
    )
    (net (code "62") (name "Net-(IC8-VREG)") (class "Default")
      (node (ref "C27") (pin "2") (pinfunction "2_2") (pintype "passive"))
      (node (ref "IC8") (pin "6") (pinfunction "VREG_6") (pintype "bidirectional"))
    )
    (net (code "63") (name "Net-(IC10-BG1)") (class "Default")
      (node (ref "IC10") (pin "4") (pinfunction "BG1_4") (pintype "bidirectional"))
      (node (ref "T18") (pin "1") (pinfunction "G_1") (pintype "passive"))
    )
    (net (code "64") (name "Net-(IC10-BG2)") (class "Default")
      (node (ref "IC10") (pin "3") (pinfunction "BG2_3") (pintype "bidirectional"))
      (node (ref "T17") (pin "1") (pinfunction "G_1") (pintype "passive"))
    )
    (net (code "65") (name "Net-(IC10-IN1)") (class "Default")
      (node (ref "AC1") (pin "1") (pinfunction "1_1") (pintype "passive"))
      (node (ref "AC1") (pin "2") (pinfunction "2_2") (pintype "passive"))
      (node (ref "IC10") (pin "8") (pinfunction "IN1_8") (pintype "bidirectional"))
      (node (ref "T16") (pin "2") (pinfunction "S_2") (pintype "passive"))
      (node (ref "T17") (pin "3") (pinfunction "D_3") (pintype "passive"))
    )
    (net (code "66") (name "Net-(IC10-IN2)") (class "Default")
      (node (ref "AC2") (pin "1") (pinfunction "1_1") (pintype "passive"))
      (node (ref "AC2") (pin "2") (pinfunction "2_2") (pintype "passive"))
      (node (ref "IC10") (pin "1") (pinfunction "IN2_1") (pintype "bidirectional"))
      (node (ref "T15") (pin "2") (pinfunction "S_2") (pintype "passive"))
      (node (ref "T18") (pin "3") (pinfunction "D_3") (pintype "passive"))
    )
    (net (code "67") (name "Net-(IC10-TG1)") (class "Default")
      (node (ref "IC10") (pin "7") (pinfunction "TG1_7") (pintype "bidirectional"))
      (node (ref "T16") (pin "1") (pinfunction "G_1") (pintype "passive"))
    )
    (net (code "68") (name "Net-(IC10-TG2)") (class "Default")
      (node (ref "IC10") (pin "2") (pinfunction "TG2_2") (pintype "bidirectional"))
      (node (ref "T15") (pin "1") (pinfunction "G_1") (pintype "passive"))
    )
    (net (code "69") (name "Net-(IC12-TRIM{slash}NR)") (class "Default")
      (node (ref "C36") (pin "1") (pinfunction "1_1") (pintype "passive"))
      (node (ref "IC12") (pin "5") (pinfunction "TRIM/NR_5") (pintype "output"))
    )
    (net (code "70") (name "Net-(IC12-VIN)") (class "Default")
      (node (ref "C37") (pin "2") (pinfunction "2_2") (pintype "passive"))
      (node (ref "C40") (pin "2") (pinfunction "2_2") (pintype "passive"))
      (node (ref "IC12") (pin "2") (pinfunction "VIN_2") (pintype "power_in"))
      (node (ref "L5") (pin "1") (pinfunction "1_1") (pintype "passive"))
    )
    (net (code "71") (name "Net-(IC14B--IN)") (class "Default")
      (node (ref "IC14") (pin "6") (pinfunction "-IN_6") (pintype "input"))
      (node (ref "R40") (pin "1") (pinfunction "1_1") (pintype "passive"))
      (node (ref "R41") (pin "1") (pinfunction "1_1") (pintype "passive"))
      (node (ref "T11") (pin "E") (pinfunction "E_E") (pintype "passive"))
    )
    (net (code "72") (name "Net-(IC14B-OUT)") (class "Default")
      (node (ref "IC14") (pin "7") (pinfunction "OUT_7") (pintype "output"))
      (node (ref "T11") (pin "B") (pinfunction "B_B") (pintype "passive"))
    )
    (net (code "73") (name "Net-(IC14C--IN)") (class "Default")
      (node (ref "C6") (pin "1") (pinfunction "1_1") (pintype "passive"))
      (node (ref "IC14") (pin "9") (pinfunction "-IN_9") (pintype "input"))
      (node (ref "R2") (pin "2") (pinfunction "2_2") (pintype "passive"))
      (node (ref "R3") (pin "2") (pinfunction "2_2") (pintype "passive"))
      (node (ref "R8") (pin "2") (pinfunction "2_2") (pintype "passive"))
    )
    (net (code "74") (name "Net-(IC14C-OUT)") (class "Default")
      (node (ref "C6") (pin "2") (pinfunction "2_2") (pintype "passive"))
      (node (ref "IC14") (pin "8") (pinfunction "OUT_8") (pintype "output"))
      (node (ref "R24") (pin "1") (pinfunction "1_1") (pintype "passive"))
    )
    (net (code "75") (name "Net-(IC15-VO)") (class "Default")
      (node (ref "C39") (pin "2") (pinfunction "2_2") (pintype "passive"))
      (node (ref "IC15") (pin "2") (pinfunction "VO_2") (pintype "passive"))
      (node (ref "L2") (pin "1") (pinfunction "1_1") (pintype "passive"))
    )
    (net (code "76") (name "Net-(IC18-ADDR)") (class "Default")
      (node (ref "C17") (pin "1") (pinfunction "1_1") (pintype "passive"))
      (node (ref "IC18") (pin "1") (pinfunction "ADDR_1") (pintype "bidirectional"))
      (node (ref "IC18") (pin "8") (pinfunction "VDD_8") (pintype "bidirectional"))
      (node (ref "L8") (pin "1") (pinfunction "1_1") (pintype "passive"))
    )
    (net (code "77") (name "Net-(L3-Pad2)") (class "Default")
      (node (ref "L3") (pin "2") (pinfunction "2_2") (pintype "passive"))
      (node (ref "V_SEL") (pin "3") (pinfunction "3_3") (pintype "passive"))
    )
    (net (code "78") (name "Net-(R11-Pad2)") (class "Default")
      (node (ref "R11") (pin "2") (pinfunction "2_2") (pintype "passive"))
      (node (ref "U$33") (pin "11/MOSI") (pinfunction "11/MOSI_11/MOSI") (pintype "bidirectional"))
    )
    (net (code "79") (name "Net-(R16-Pad2)") (class "Default")
      (node (ref "R16") (pin "2") (pinfunction "2_2") (pintype "passive"))
      (node (ref "U$33") (pin "27") (pinfunction "27_27") (pintype "bidirectional"))
    )
    (net (code "80") (name "Net-(R18-Pad2)") (class "Default")
      (node (ref "R18") (pin "2") (pinfunction "2_2") (pintype "passive"))
      (node (ref "R25") (pin "1") (pinfunction "1_1") (pintype "passive"))
    )
    (net (code "81") (name "Net-(R25-Pad2)") (class "Default")
      (node (ref "R25") (pin "2") (pinfunction "2_2") (pintype "passive"))
      (node (ref "R26") (pin "1") (pinfunction "1_1") (pintype "passive"))
    )
    (net (code "82") (name "Net-(R28-Pad2)") (class "Default")
      (node (ref "R28") (pin "2") (pinfunction "2_2") (pintype "passive"))
      (node (ref "SV5") (pin "1") (pinfunction "1_1") (pintype "passive"))
    )
    (net (code "83") (name "Net-(R29-Pad2)") (class "Default")
      (node (ref "R29") (pin "2") (pinfunction "2_2") (pintype "passive"))
      (node (ref "SV5") (pin "2") (pinfunction "2_2") (pintype "passive"))
    )
    (net (code "84") (name "Net-(R44-Pad1)") (class "Default")
      (node (ref "R44") (pin "1") (pinfunction "1_1") (pintype "passive"))
      (node (ref "R5") (pin "E2") (pinfunction "E2_E2") (pintype "passive"))
    )
    (net (code "85") (name "Net-(R45-Pad2)") (class "Default")
      (node (ref "R45") (pin "2") (pinfunction "2_2") (pintype "passive"))
      (node (ref "R5") (pin "E1") (pinfunction "E1_E1") (pintype "passive"))
    )
    (net (code "86") (name "Net-(T1-D)") (class "Default")
      (node (ref "D8") (pin "A") (pinfunction "A_A") (pintype "passive"))
      (node (ref "REL1") (pin "+") (pinfunction "+_+") (pintype "passive"))
      (node (ref "T1") (pin "3") (pinfunction "D_3") (pintype "passive"))
    )
    (net (code "87") (name "Net-(T3-C)") (class "Default")
      (node (ref "C11") (pin "1") (pinfunction "1_1") (pintype "passive"))
      (node (ref "D14") (pin "C") (pinfunction "C_C") (pintype "passive"))
      (node (ref "R5") (pin "I1") (pinfunction "I1_I1") (pintype "passive"))
      (node (ref "T3") (pin "2") (pinfunction "C_2") (pintype "passive"))
      (node (ref "T5") (pin "C") (pinfunction "C_C") (pintype "passive"))
      (node (ref "T6") (pin "C") (pinfunction "C_C") (pintype "passive"))
      (node (ref "T7") (pin "2") (pinfunction "C_2") (pintype "passive"))
    )
    (net (code "88") (name "Net-(T3-E)") (class "Default")
      (node (ref "SJ1") (pin "1") (pinfunction "1_1") (pintype "passive"))
      (node (ref "T3") (pin "1") (pinfunction "E_1") (pintype "passive"))
      (node (ref "T5") (pin "B") (pinfunction "B_B") (pintype "passive"))
    )
    (net (code "89") (name "Net-(T4-D)") (class "Default")
      (node (ref "SINK") (pin "2") (pinfunction "2_2") (pintype "passive"))
      (node (ref "T4") (pin "3") (pinfunction "D_3") (pintype "passive"))
    )
    (net (code "90") (name "Net-(T4-S)") (class "Default")
      (node (ref "R13") (pin "2") (pinfunction "2_2") (pintype "passive"))
      (node (ref "R14") (pin "1") (pinfunction "1_1") (pintype "passive"))
      (node (ref "T4") (pin "2") (pinfunction "S_2") (pintype "passive"))
    )
    (net (code "91") (name "Net-(T7-E)") (class "Default")
      (node (ref "SJ1") (pin "2") (pinfunction "2_2") (pintype "passive"))
      (node (ref "T6") (pin "B") (pinfunction "B_B") (pintype "passive"))
      (node (ref "T7") (pin "1") (pinfunction "E_1") (pintype "passive"))
    )
    (net (code "92") (name "Net-(T12-D)") (class "Default")
      (node (ref "SV5") (pin "3") (pinfunction "3_3") (pintype "passive"))
      (node (ref "T12") (pin "3") (pinfunction "D_3") (pintype "passive"))
    )
    (net (code "93") (name "Net-(T13-D)") (class "Default")
      (node (ref "SV5") (pin "4") (pinfunction "4_4") (pintype "passive"))
      (node (ref "T13") (pin "3") (pinfunction "D_3") (pintype "passive"))
    )
    (net (code "94") (name "Net-(T14-D)") (class "Default")
      (node (ref "SV5") (pin "5") (pinfunction "5_5") (pintype "passive"))
      (node (ref "T14") (pin "3") (pinfunction "D_3") (pintype "passive"))
    )
    (net (code "95") (name "OVRCRNT_DET") (class "Default")
      (node (ref "C5") (pin "2") (pinfunction "2_2") (pintype "passive"))
      (node (ref "IC14") (pin "14") (pinfunction "OUT_14") (pintype "output"))
      (node (ref "IC14") (pin "3") (pinfunction "+IN_3") (pintype "input"))
      (node (ref "I_PROT") (pin "2") (pinfunction "2_2") (pintype "passive"))
    )
    (net (code "96") (name "OVRCRNT_DET_BUF") (class "Default")
      (node (ref "IC14") (pin "1") (pinfunction "OUT_1") (pintype "output"))
      (node (ref "IC14") (pin "2") (pinfunction "-IN_2") (pintype "input"))
      (node (ref "R23") (pin "2") (pinfunction "2_2") (pintype "passive"))
    )
    (net (code "97") (name "P_VSS") (class "Default")
      (node (ref "C1") (pin "-") (pinfunction "-_-") (pintype "passive"))
      (node (ref "C2") (pin "-") (pinfunction "-_-") (pintype "passive"))
      (node (ref "C53") (pin "2") (pinfunction "2_2") (pintype "passive"))
      (node (ref "IC10") (pin "5") (pinfunction "OUTN_5") (pintype "bidirectional"))
      (node (ref "T17") (pin "2") (pinfunction "S_2") (pintype "passive"))
      (node (ref "T18") (pin "2") (pinfunction "S_2") (pintype "passive"))
    )
    (net (code "98") (name "REL-OUT") (class "Default")
      (node (ref "R48") (pin "2") (pinfunction "2_2") (pintype "passive"))
      (node (ref "T1") (pin "1") (pinfunction "G_1") (pintype "passive"))
      (node (ref "U$33") (pin "30") (pinfunction "30_30") (pintype "bidirectional"))
    )
    (net (code "99") (name "SCK") (class "Default")
      (node (ref "DSPLY") (pin "4") (pinfunction "4_4") (pintype "passive"))
      (node (ref "IC3") (pin "2") (pinfunction "SCLK_2") (pintype "input"))
      (node (ref "IC7") (pin "2") (pinfunction "SCLK_2") (pintype "input"))
      (node (ref "R16") (pin "1") (pinfunction "1_1") (pintype "passive"))
    )
    (net (code "100") (name "SCL") (class "Default")
      (node (ref "IC18") (pin "10") (pinfunction "SCL_10") (pintype "bidirectional"))
      (node (ref "IC19") (pin "10") (pinfunction "SCL_10") (pintype "bidirectional"))
      (node (ref "R4") (pin "1") (pinfunction "1_1") (pintype "passive"))
      (node (ref "U$33") (pin "19/A5/SCL") (pinfunction "19/A5/SCL_19/A5/SCL") (pintype "bidirectional"))
    )
    (net (code "101") (name "SDA") (class "Default")
      (node (ref "IC18") (pin "9") (pinfunction "SDA_9") (pintype "bidirectional"))
      (node (ref "IC19") (pin "9") (pinfunction "SDA_9") (pintype "bidirectional"))
      (node (ref "R6") (pin "2") (pinfunction "2_2") (pintype "passive"))
      (node (ref "U$33") (pin "18/A4/SDA") (pinfunction "18/A4/SDA_18/A4/SDA") (pintype "bidirectional"))
    )
    (net (code "102") (name "TH0") (class "Default")
      (node (ref "C49") (pin "2") (pinfunction "2_2") (pintype "passive"))
      (node (ref "R36") (pin "2") (pinfunction "2_2") (pintype "passive"))
      (node (ref "R42") (pin "2") (pinfunction "2_2") (pintype "passive"))
      (node (ref "SV2") (pin "1") (pinfunction "1_1") (pintype "passive"))
    )
    (net (code "103") (name "TH0_ADC") (class "Default")
      (node (ref "IC19") (pin "4") (pinfunction "AIN0_4") (pintype "bidirectional"))
      (node (ref "SV1") (pin "1") (pinfunction "1_1") (pintype "passive"))
    )
    (net (code "104") (name "VDAC_CS") (class "Default")
      (node (ref "IC3") (pin "1") (pinfunction "SYNC_1") (pintype "input"))
      (node (ref "U$33") (pin "14/A0") (pinfunction "14/A0_14/A0") (pintype "bidirectional"))
    )
    (net (code "105") (name "VREF4096") (class "Default")
      (node (ref "C34") (pin "1") (pinfunction "1_1") (pintype "passive"))
      (node (ref "C41") (pin "1") (pinfunction "1_1") (pintype "passive"))
      (node (ref "C7") (pin "1") (pinfunction "1_1") (pintype "passive"))
      (node (ref "C8") (pin "1") (pinfunction "1_1") (pintype "passive"))
      (node (ref "C9") (pin "1") (pinfunction "1_1") (pintype "passive"))
      (node (ref "IC12") (pin "6") (pinfunction "VOUT_6") (pintype "output"))
      (node (ref "IC3") (pin "4") (pinfunction "AVDD/VREF_4") (pintype "power_in"))
      (node (ref "IC7") (pin "4") (pinfunction "AVDD/VREF_4") (pintype "power_in"))
      (node (ref "R19") (pin "1") (pinfunction "1_1") (pintype "passive"))
    )
    (net (code "106") (name "VSET") (class "Default")
      (node (ref "IC14") (pin "10") (pinfunction "+IN_10") (pintype "input"))
      (node (ref "IC3") (pin "6") (pinfunction "VOUT_6") (pintype "output"))
    )
    (net (code "107") (name "VSS") (class "Default")
      (node (ref "C12") (pin "1") (pinfunction "1_1") (pintype "passive"))
      (node (ref "C16") (pin "1") (pinfunction "1_1") (pintype "passive"))
      (node (ref "C19") (pin "1") (pinfunction "1_1") (pintype "passive"))
      (node (ref "C20") (pin "1") (pinfunction "1_1") (pintype "passive"))
      (node (ref "C23") (pin "2") (pinfunction "2_2") (pintype "passive"))
      (node (ref "C24") (pin "2") (pinfunction "2_2") (pintype "passive"))
      (node (ref "C30") (pin "2") (pinfunction "2_2") (pintype "passive"))
      (node (ref "C31") (pin "2") (pinfunction "2_2") (pintype "passive"))
      (node (ref "C33") (pin "-") (pinfunction "-_-") (pintype "passive"))
      (node (ref "C38") (pin "2") (pinfunction "2_2") (pintype "passive"))
      (node (ref "C39") (pin "1") (pinfunction "1_1") (pintype "passive"))
      (node (ref "C44") (pin "-") (pinfunction "-_-") (pintype "passive"))
      (node (ref "DSPLY") (pin "7") (pinfunction "7_7") (pintype "passive"))
      (node (ref "ESP/BTNS") (pin "6") (pinfunction "6_6") (pintype "passive"))
      (node (ref "FAN") (pin "4") (pinfunction "4_4") (pintype "passive"))
      (node (ref "IC15") (pin "1") (pinfunction "GND_1") (pintype "passive"))
      (node (ref "IC4") (pin "2") (pinfunction "GND_2") (pintype "passive"))
      (node (ref "IC6") (pin "2") (pinfunction "GND_2") (pintype "passive"))
      (node (ref "R48") (pin "1") (pinfunction "1_1") (pintype "passive"))
      (node (ref "SG1") (pin "-") (pinfunction "2_-") (pintype "passive"))
      (node (ref "T1") (pin "2") (pinfunction "S_2") (pintype "passive"))
      (node (ref "T12") (pin "2") (pinfunction "S_2") (pintype "passive"))
      (node (ref "T13") (pin "2") (pinfunction "S_2") (pintype "passive"))
      (node (ref "T14") (pin "2") (pinfunction "S_2") (pintype "passive"))
      (node (ref "U$33") (pin "GND") (pinfunction "GND_GND") (pintype "bidirectional"))
      (node (ref "VSS") (pin "MP") (pinfunction "MP_MP") (pintype "passive"))
    )
    (net (code "108") (name "V_OUT_CON") (class "Default")
      (node (ref "REL1") (pin "P1") (pinfunction "P_P1") (pintype "passive"))
      (node (ref "VOUT") (pin "1") (pinfunction "1_1") (pintype "passive"))
      (node (ref "VOUT") (pin "2") (pinfunction "2_2") (pintype "passive"))
    )
    (net (code "109") (name "unconnected-(FAN-Pad2)") (class "Default")
      (node (ref "FAN") (pin "2") (pinfunction "2_2") (pintype "passive"))
    )
    (net (code "110") (name "unconnected-(H1-MOUNT-PadB3,3)") (class "Default")
      (node (ref "H1") (pin "B3,3") (pinfunction "MOUNT_B3,3") (pintype "passive"))
    )
    (net (code "111") (name "unconnected-(H2-MOUNT-PadB3,3)") (class "Default")
      (node (ref "H2") (pin "B3,3") (pinfunction "MOUNT_B3,3") (pintype "passive"))
    )
    (net (code "112") (name "unconnected-(H3-MOUNT-PadB3,3)") (class "Default")
      (node (ref "H3") (pin "B3,3") (pinfunction "MOUNT_B3,3") (pintype "passive"))
    )
    (net (code "113") (name "unconnected-(H4-MOUNT-PadB3,3)") (class "Default")
      (node (ref "H4") (pin "B3,3") (pinfunction "MOUNT_B3,3") (pintype "passive"))
    )
    (net (code "114") (name "unconnected-(IC1-NC-Pad4)") (class "Default")
      (node (ref "IC1") (pin "4") (pinfunction "NC_4") (pintype "input"))
    )
    (net (code "115") (name "unconnected-(IC9-NC-Pad4)") (class "Default")
      (node (ref "IC9") (pin "4") (pinfunction "NC_4") (pintype "input"))
    )
    (net (code "116") (name "unconnected-(IC12-DNC-Pad1)") (class "Default")
      (node (ref "IC12") (pin "1") (pinfunction "DNC_1") (pintype "no_connect"))
    )
    (net (code "117") (name "unconnected-(IC12-DNC2-Pad8)") (class "Default")
      (node (ref "IC12") (pin "8") (pinfunction "DNC2_8") (pintype "no_connect"))
    )
    (net (code "118") (name "unconnected-(IC12-NC-Pad7)") (class "Default")
      (node (ref "IC12") (pin "7") (pinfunction "NC_7") (pintype "no_connect"))
    )
    (net (code "119") (name "unconnected-(IC12-TEMP-Pad3)") (class "Default")
      (node (ref "IC12") (pin "3") (pinfunction "TEMP_3") (pintype "output"))
    )
    (net (code "120") (name "unconnected-(IC18-ALERT{slash}RDY-Pad2)") (class "Default")
      (node (ref "IC18") (pin "2") (pinfunction "ALERT/RDY_2") (pintype "bidirectional"))
    )
    (net (code "121") (name "unconnected-(IC19-AIN1-Pad5)") (class "Default")
      (node (ref "IC19") (pin "5") (pinfunction "AIN1_5") (pintype "bidirectional"))
    )
    (net (code "122") (name "unconnected-(IC19-ALERT{slash}RDY-Pad2)") (class "Default")
      (node (ref "IC19") (pin "2") (pinfunction "ALERT/RDY_2") (pintype "bidirectional"))
    )
    (net (code "123") (name "unconnected-(REL1B-O-PadO1)") (class "Default")
      (node (ref "REL1") (pin "O1") (pinfunction "O_O1") (pintype "passive"))
    )
    (net (code "124") (name "unconnected-(REL1C-O-PadO2)") (class "Default")
      (node (ref "REL1") (pin "O2") (pinfunction "O_O2") (pintype "passive"))
    )
    (net (code "125") (name "unconnected-(U$33-A21{slash}DAC0-Pad21{slash}DAC0)") (class "Default")
      (node (ref "U$33") (pin "21/DAC0") (pinfunction "A21/DAC0_21/DAC0") (pintype "bidirectional"))
    )
    (net (code "126") (name "unconnected-(U$33-Pad0{slash}RX)") (class "Default")
      (node (ref "U$33") (pin "0/RX") (pinfunction "0/RX_0/RX") (pintype "bidirectional"))
    )
    (net (code "127") (name "unconnected-(U$33-Pad1{slash}TX)") (class "Default")
      (node (ref "U$33") (pin "1/TX") (pinfunction "1/TX_1/TX") (pintype "bidirectional"))
    )
    (net (code "128") (name "unconnected-(U$33-Pad3V3)") (class "Default")
      (node (ref "U$33") (pin "3V3") (pinfunction "3V3_3V3") (pintype "bidirectional"))
    )
    (net (code "129") (name "unconnected-(U$33-Pad3V3_2)") (class "Default")
      (node (ref "U$33") (pin "3V3_2") (pinfunction "3V3_2_3V3_2") (pintype "bidirectional"))
    )
    (net (code "130") (name "unconnected-(U$33-Pad9{slash}CS)") (class "Default")
      (node (ref "U$33") (pin "9/CS") (pinfunction "9/CS_9/CS") (pintype "bidirectional"))
    )
    (net (code "131") (name "unconnected-(U$33-Pad10{slash}CS)") (class "Default")
      (node (ref "U$33") (pin "10/CS") (pinfunction "10/CS_10/CS") (pintype "bidirectional"))
    )
    (net (code "132") (name "unconnected-(U$33-Pad12{slash}MISO)") (class "Default")
      (node (ref "U$33") (pin "12/MISO") (pinfunction "12/MISO_12/MISO") (pintype "bidirectional"))
    )
    (net (code "133") (name "unconnected-(U$33-Pad13{slash}SCK)") (class "Default")
      (node (ref "U$33") (pin "13/SCK") (pinfunction "13/SCK_13/SCK") (pintype "bidirectional"))
    )
    (net (code "134") (name "unconnected-(U$33-Pad20{slash}A6)") (class "Default")
      (node (ref "U$33") (pin "20/A6") (pinfunction "20/A6_20/A6") (pintype "bidirectional"))
    )
    (net (code "135") (name "unconnected-(U$33-Pad25)") (class "Default")
      (node (ref "U$33") (pin "25") (pinfunction "25_25") (pintype "bidirectional"))
    )
    (net (code "136") (name "unconnected-(U$33-Pad36{slash}A17)") (class "Default")
      (node (ref "U$33") (pin "36/A17") (pinfunction "36/A17_36/A17") (pintype "bidirectional"))
    )
    (net (code "137") (name "unconnected-(U$33-Pad37{slash}A18)") (class "Default")
      (node (ref "U$33") (pin "37/A18") (pinfunction "37/A18_37/A18") (pintype "bidirectional"))
    )
    (net (code "138") (name "unconnected-(U$33-Pad38{slash}A19)") (class "Default")
      (node (ref "U$33") (pin "38/A19") (pinfunction "38/A19_38/A19") (pintype "bidirectional"))
    )
    (net (code "139") (name "unconnected-(U$33-Pad39{slash}A20)") (class "Default")
      (node (ref "U$33") (pin "39/A20") (pinfunction "39/A20_39/A20") (pintype "bidirectional"))
    )
    (net (code "140") (name "unconnected-(U$33-PadA10)") (class "Default")
      (node (ref "U$33") (pin "A10") (pinfunction "A10_A10") (pintype "bidirectional"))
    )
    (net (code "141") (name "unconnected-(U$33-PadA11)") (class "Default")
      (node (ref "U$33") (pin "A11") (pinfunction "A11_A11") (pintype "bidirectional"))
    )
    (net (code "142") (name "unconnected-(U$33-PadA22{slash}DAC1)") (class "Default")
      (node (ref "U$33") (pin "A22/DAC1") (pinfunction "A22/DAC1_A22/DAC1") (pintype "bidirectional"))
    )
    (net (code "143") (name "unconnected-(U$33-PadAREF)") (class "Default")
      (node (ref "U$33") (pin "AREF") (pinfunction "AREF_AREF") (pintype "bidirectional"))
    )
    (net (code "144") (name "unconnected-(U$33-PadGND3)") (class "Default")
      (node (ref "U$33") (pin "GND3") (pinfunction "GND3_GND3") (pintype "bidirectional"))
    )
    (net (code "145") (name "unconnected-(U$33-PadPROG)") (class "Default")
      (node (ref "U$33") (pin "PROG") (pinfunction "PROG_PROG") (pintype "bidirectional"))
    )
    (net (code "146") (name "unconnected-(U$33-PadRESET)") (class "Default")
      (node (ref "U$33") (pin "RESET") (pinfunction "RESET_RESET") (pintype "bidirectional"))
    )
    (net (code "147") (name "unconnected-(U$33-PadU5V)") (class "Default")
      (node (ref "U$33") (pin "U5V") (pinfunction "U5V_U5V") (pintype "bidirectional"))
    )
    (net (code "148") (name "unconnected-(U$33-PadUD+)") (class "Default")
      (node (ref "U$33") (pin "UD+") (pinfunction "UD+_UD+") (pintype "bidirectional"))
    )
    (net (code "149") (name "unconnected-(U$33-PadUD-)") (class "Default")
      (node (ref "U$33") (pin "UD-") (pinfunction "UD-_UD-") (pintype "bidirectional"))
    )
    (net (code "150") (name "unconnected-(U$33-PadUGND1)") (class "Default")
      (node (ref "U$33") (pin "UGND1") (pinfunction "UGND1_UGND1") (pintype "bidirectional"))
    )
    (net (code "151") (name "unconnected-(U$33-PadUGND2)") (class "Default")
      (node (ref "U$33") (pin "UGND2") (pinfunction "UGND2_UGND2") (pintype "bidirectional"))
    )
    (net (code "152") (name "unconnected-(U$33-PadVBAT)") (class "Default")
      (node (ref "U$33") (pin "VBAT") (pinfunction "VBAT_VBAT") (pintype "bidirectional"))
    )
    (net (code "153") (name "unconnected-(U$33-PadVUSB)") (class "Default")
      (node (ref "U$33") (pin "VUSB") (pinfunction "VUSB_VUSB") (pintype "bidirectional"))
    )
    (net (code "154") (name "unconnected-(V_SEL-Pad1)") (class "Default")
      (node (ref "V_SEL") (pin "1") (pinfunction "1_1") (pintype "passive"))
    )
  )
)
